# oresat0-1u-backplane.net
KiCad netlist of a schematic drawn in EAGLE
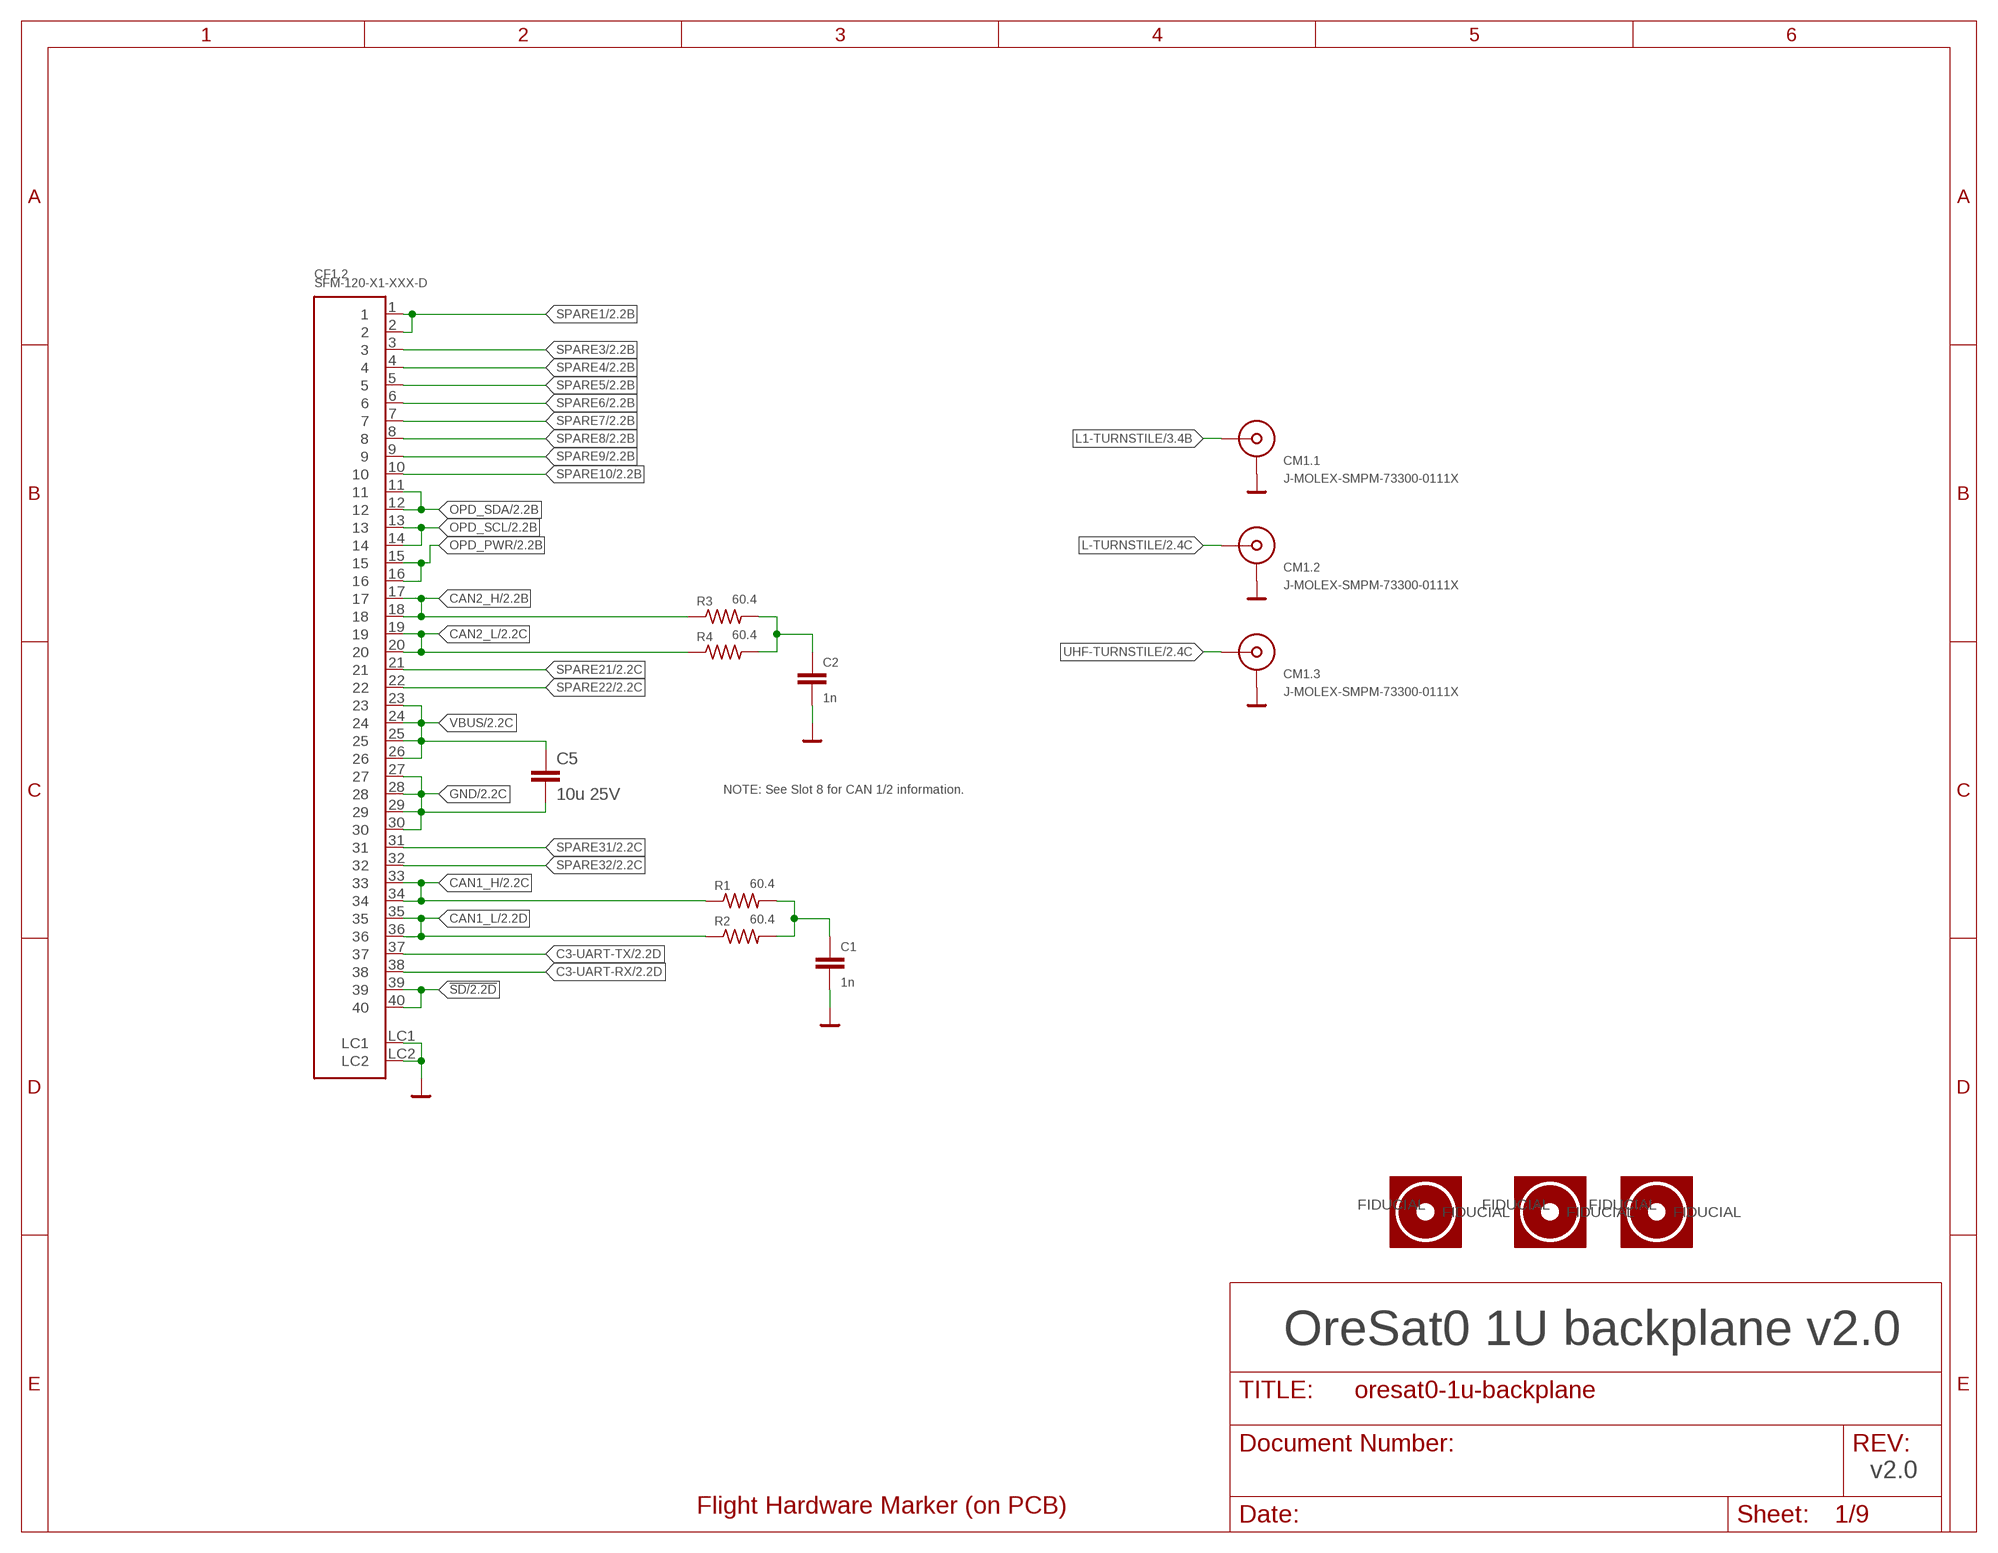
[diagram p0: schematic, sheet 1]
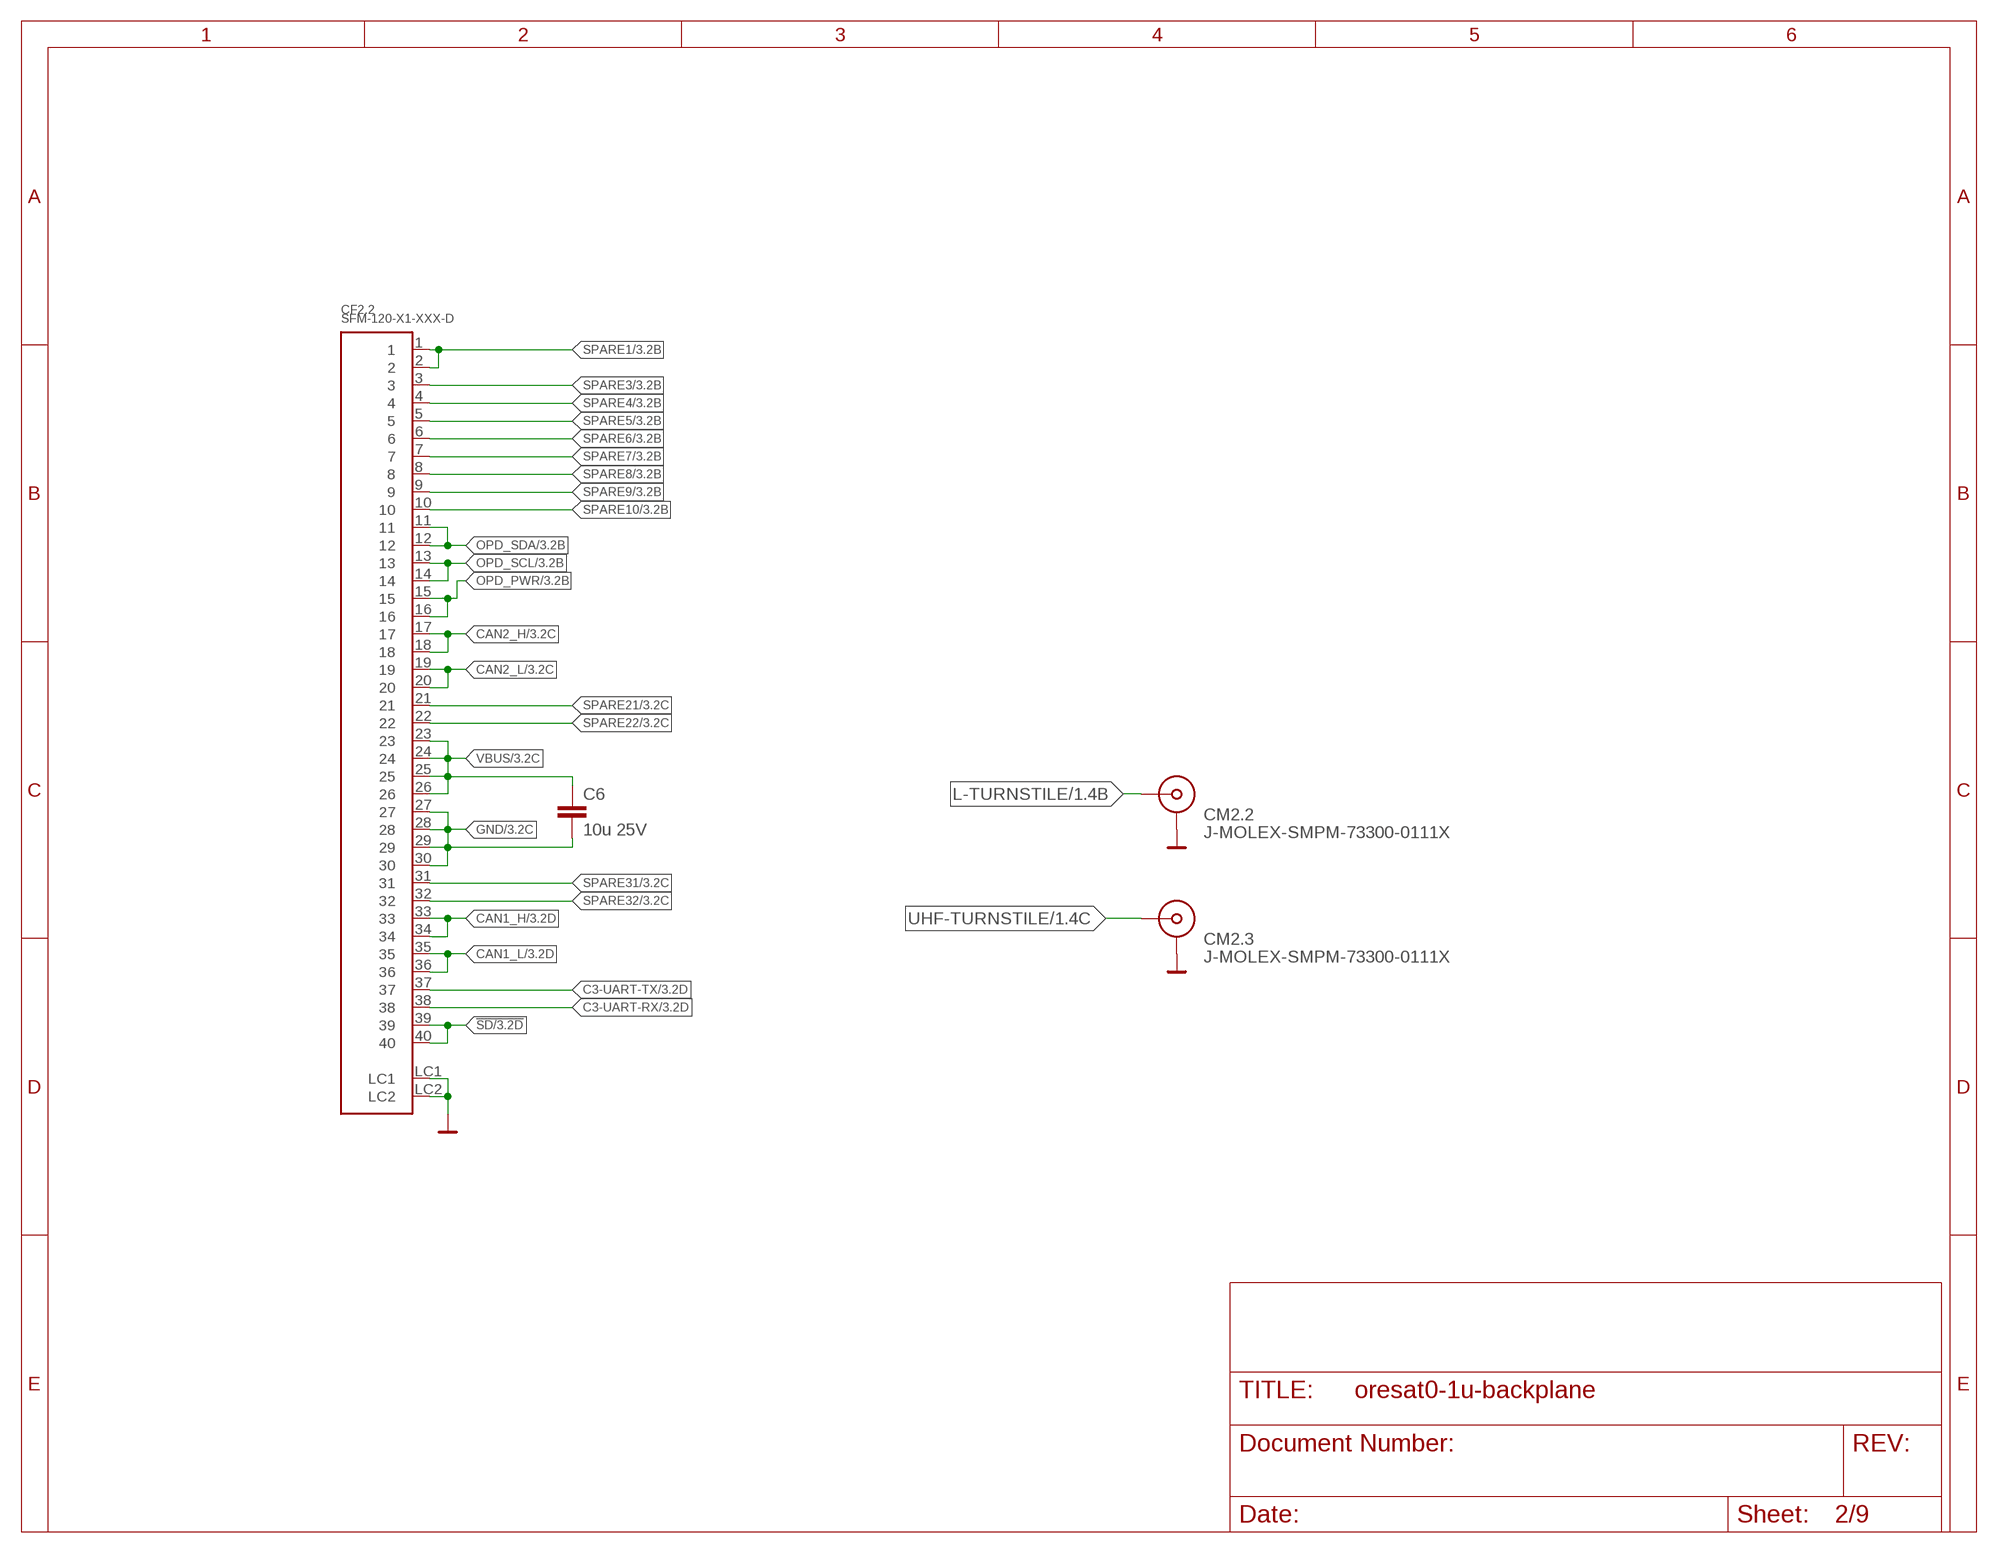
[diagram p1: schematic, sheet 2]
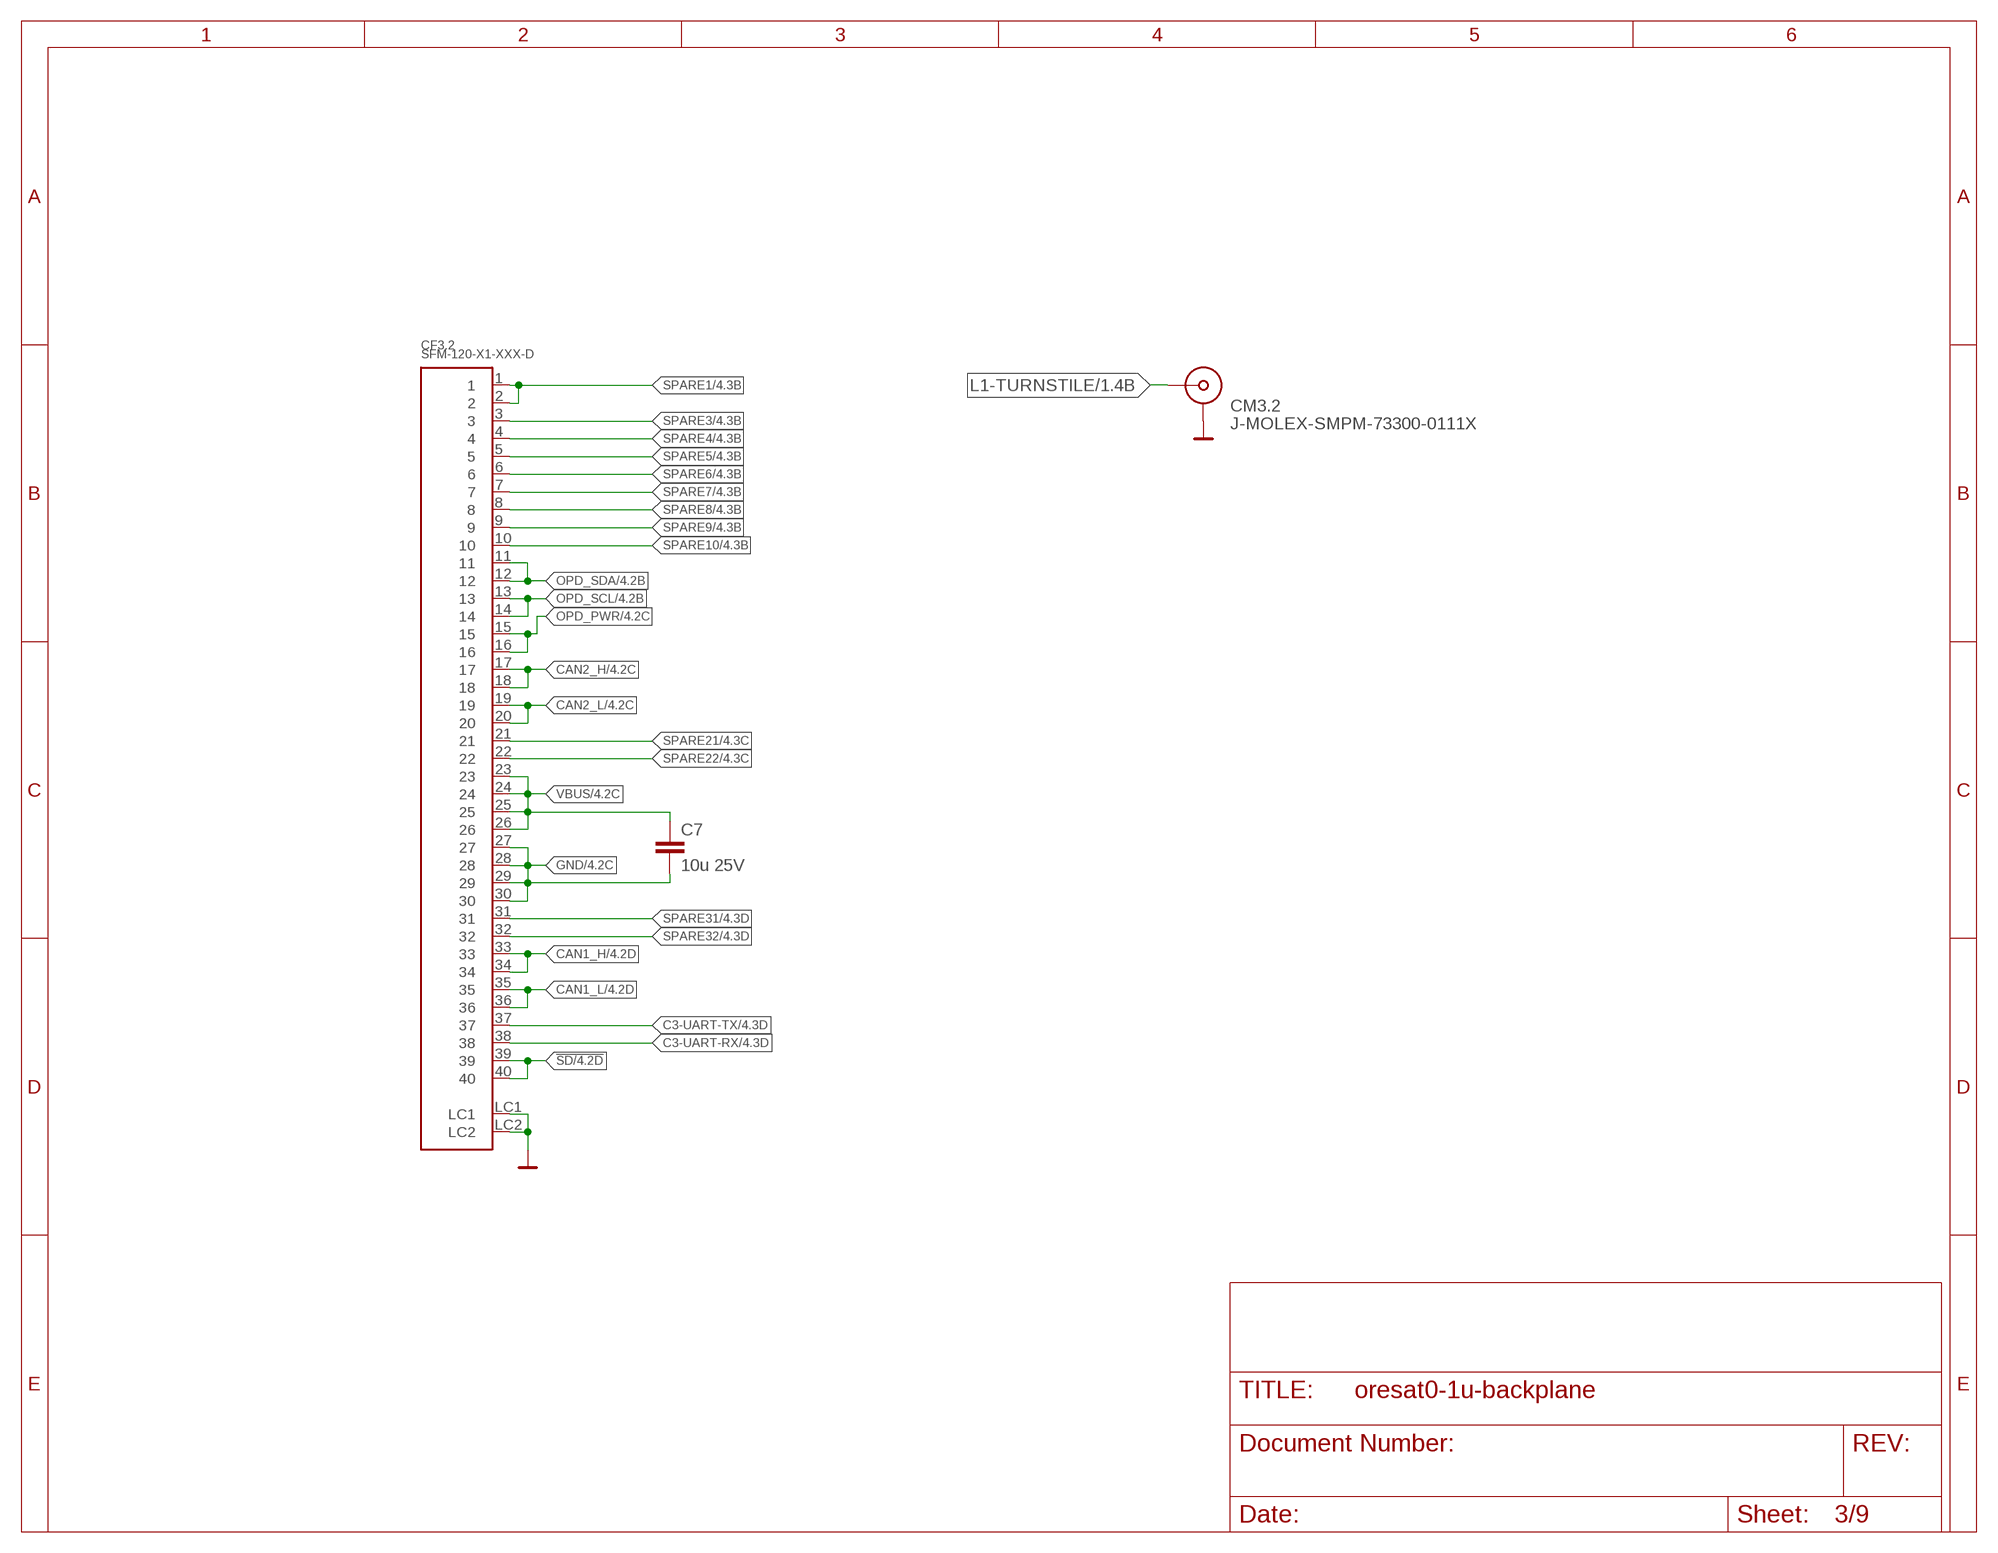
[diagram p2: schematic, sheet 3]
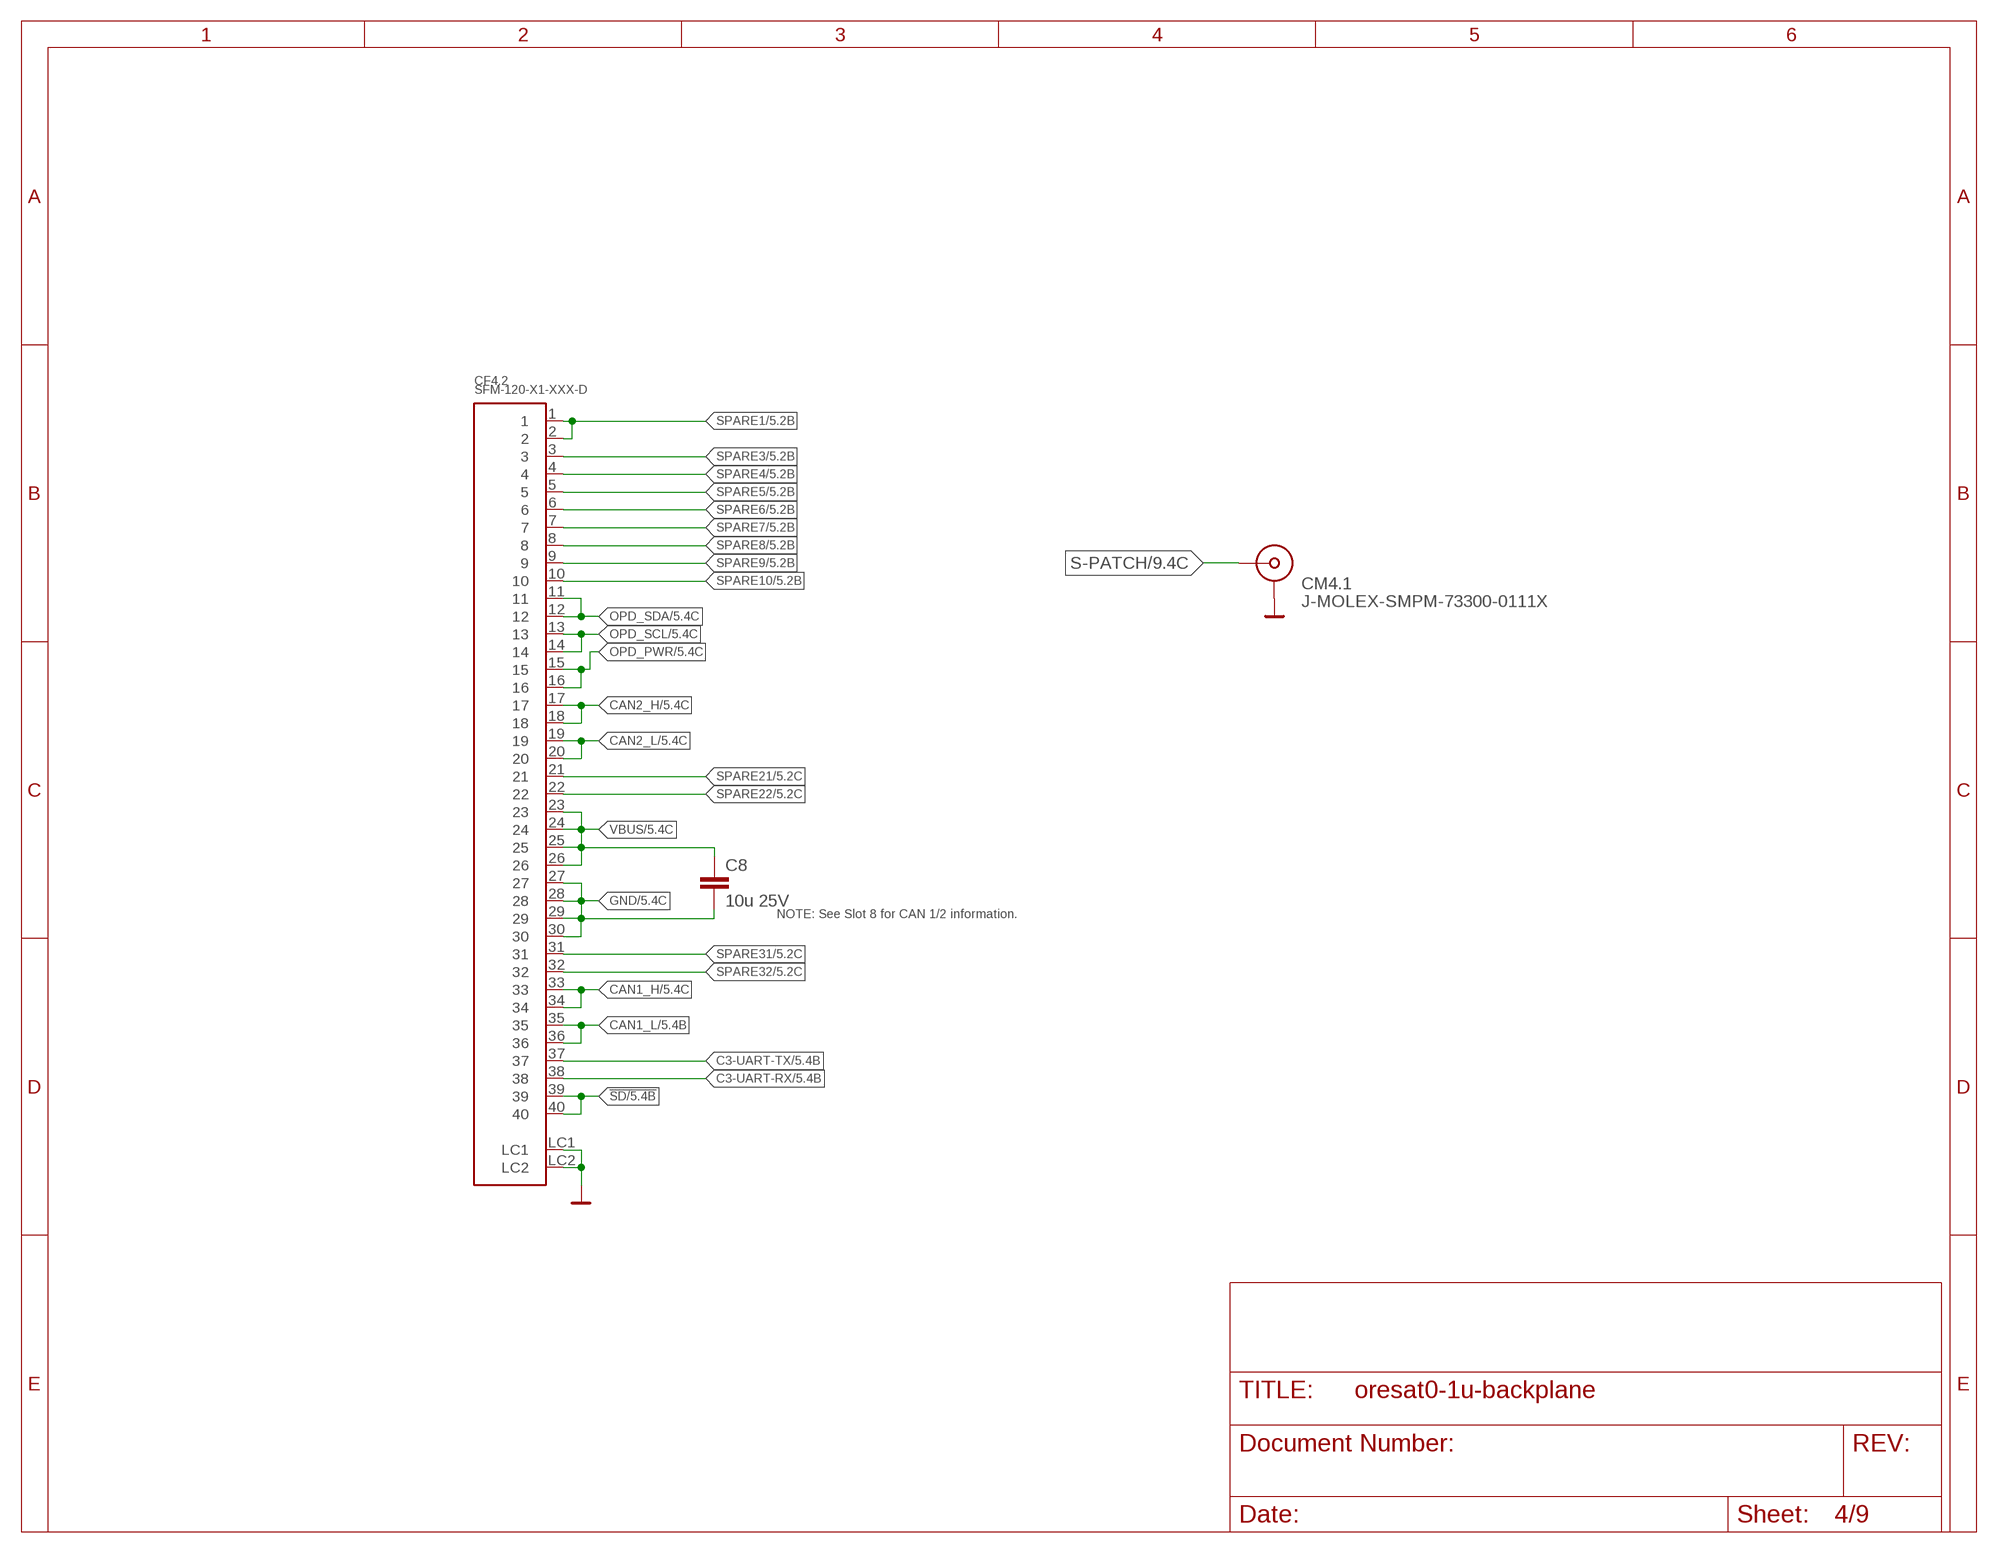
[diagram p3: schematic, sheet 4]
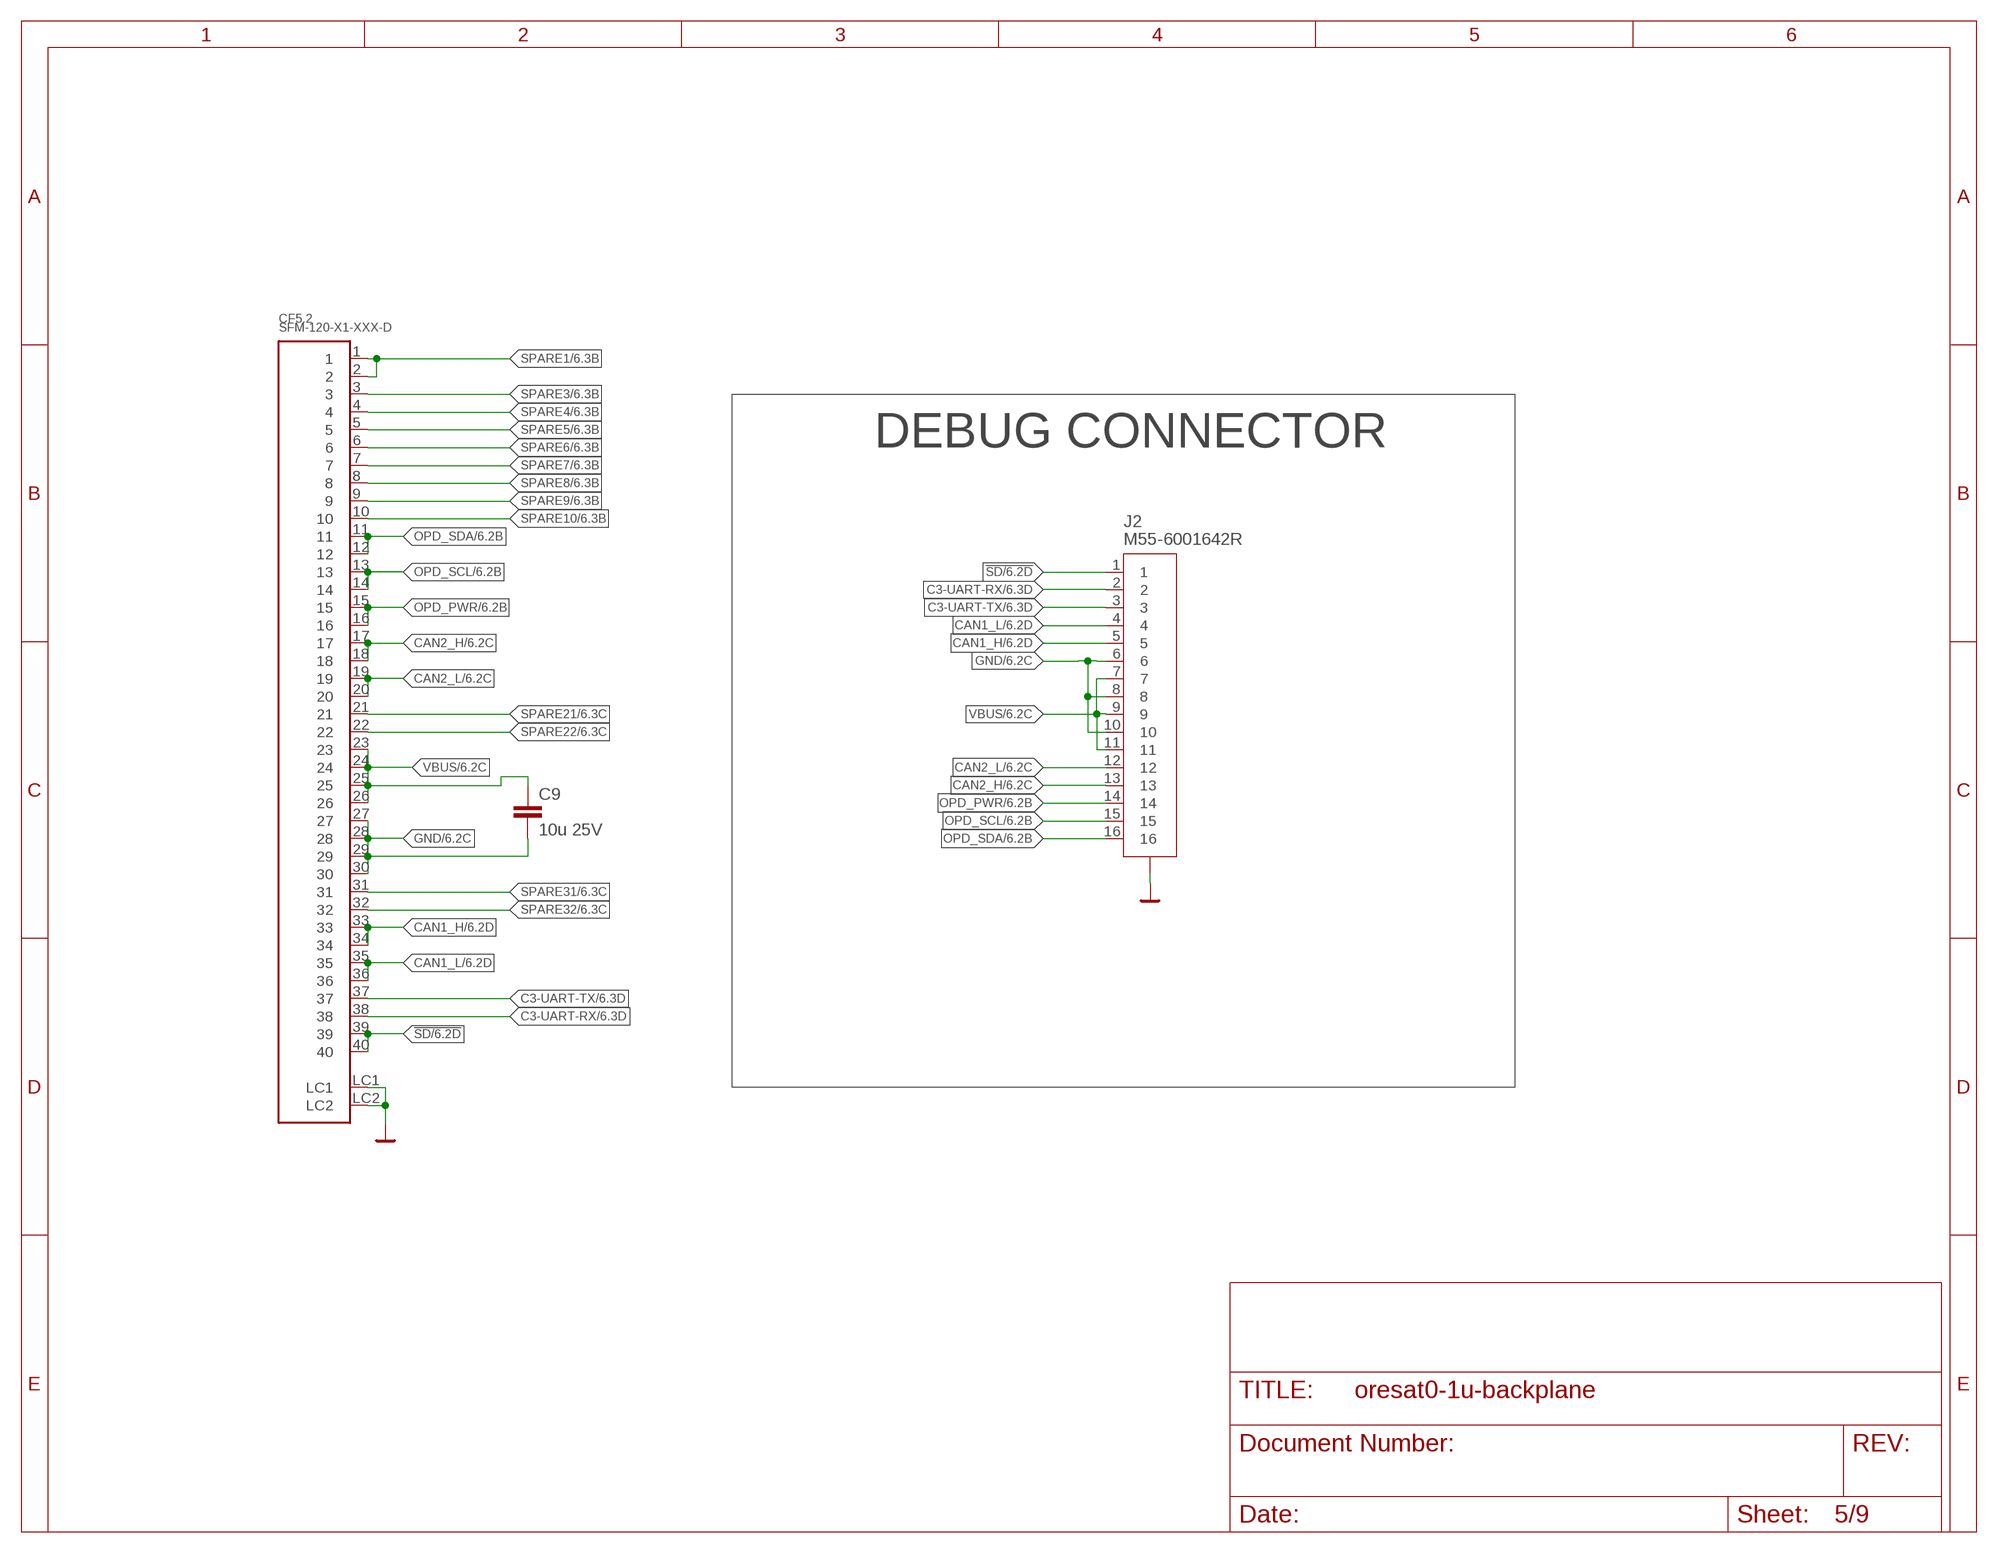
[diagram p4: schematic, sheet 5]
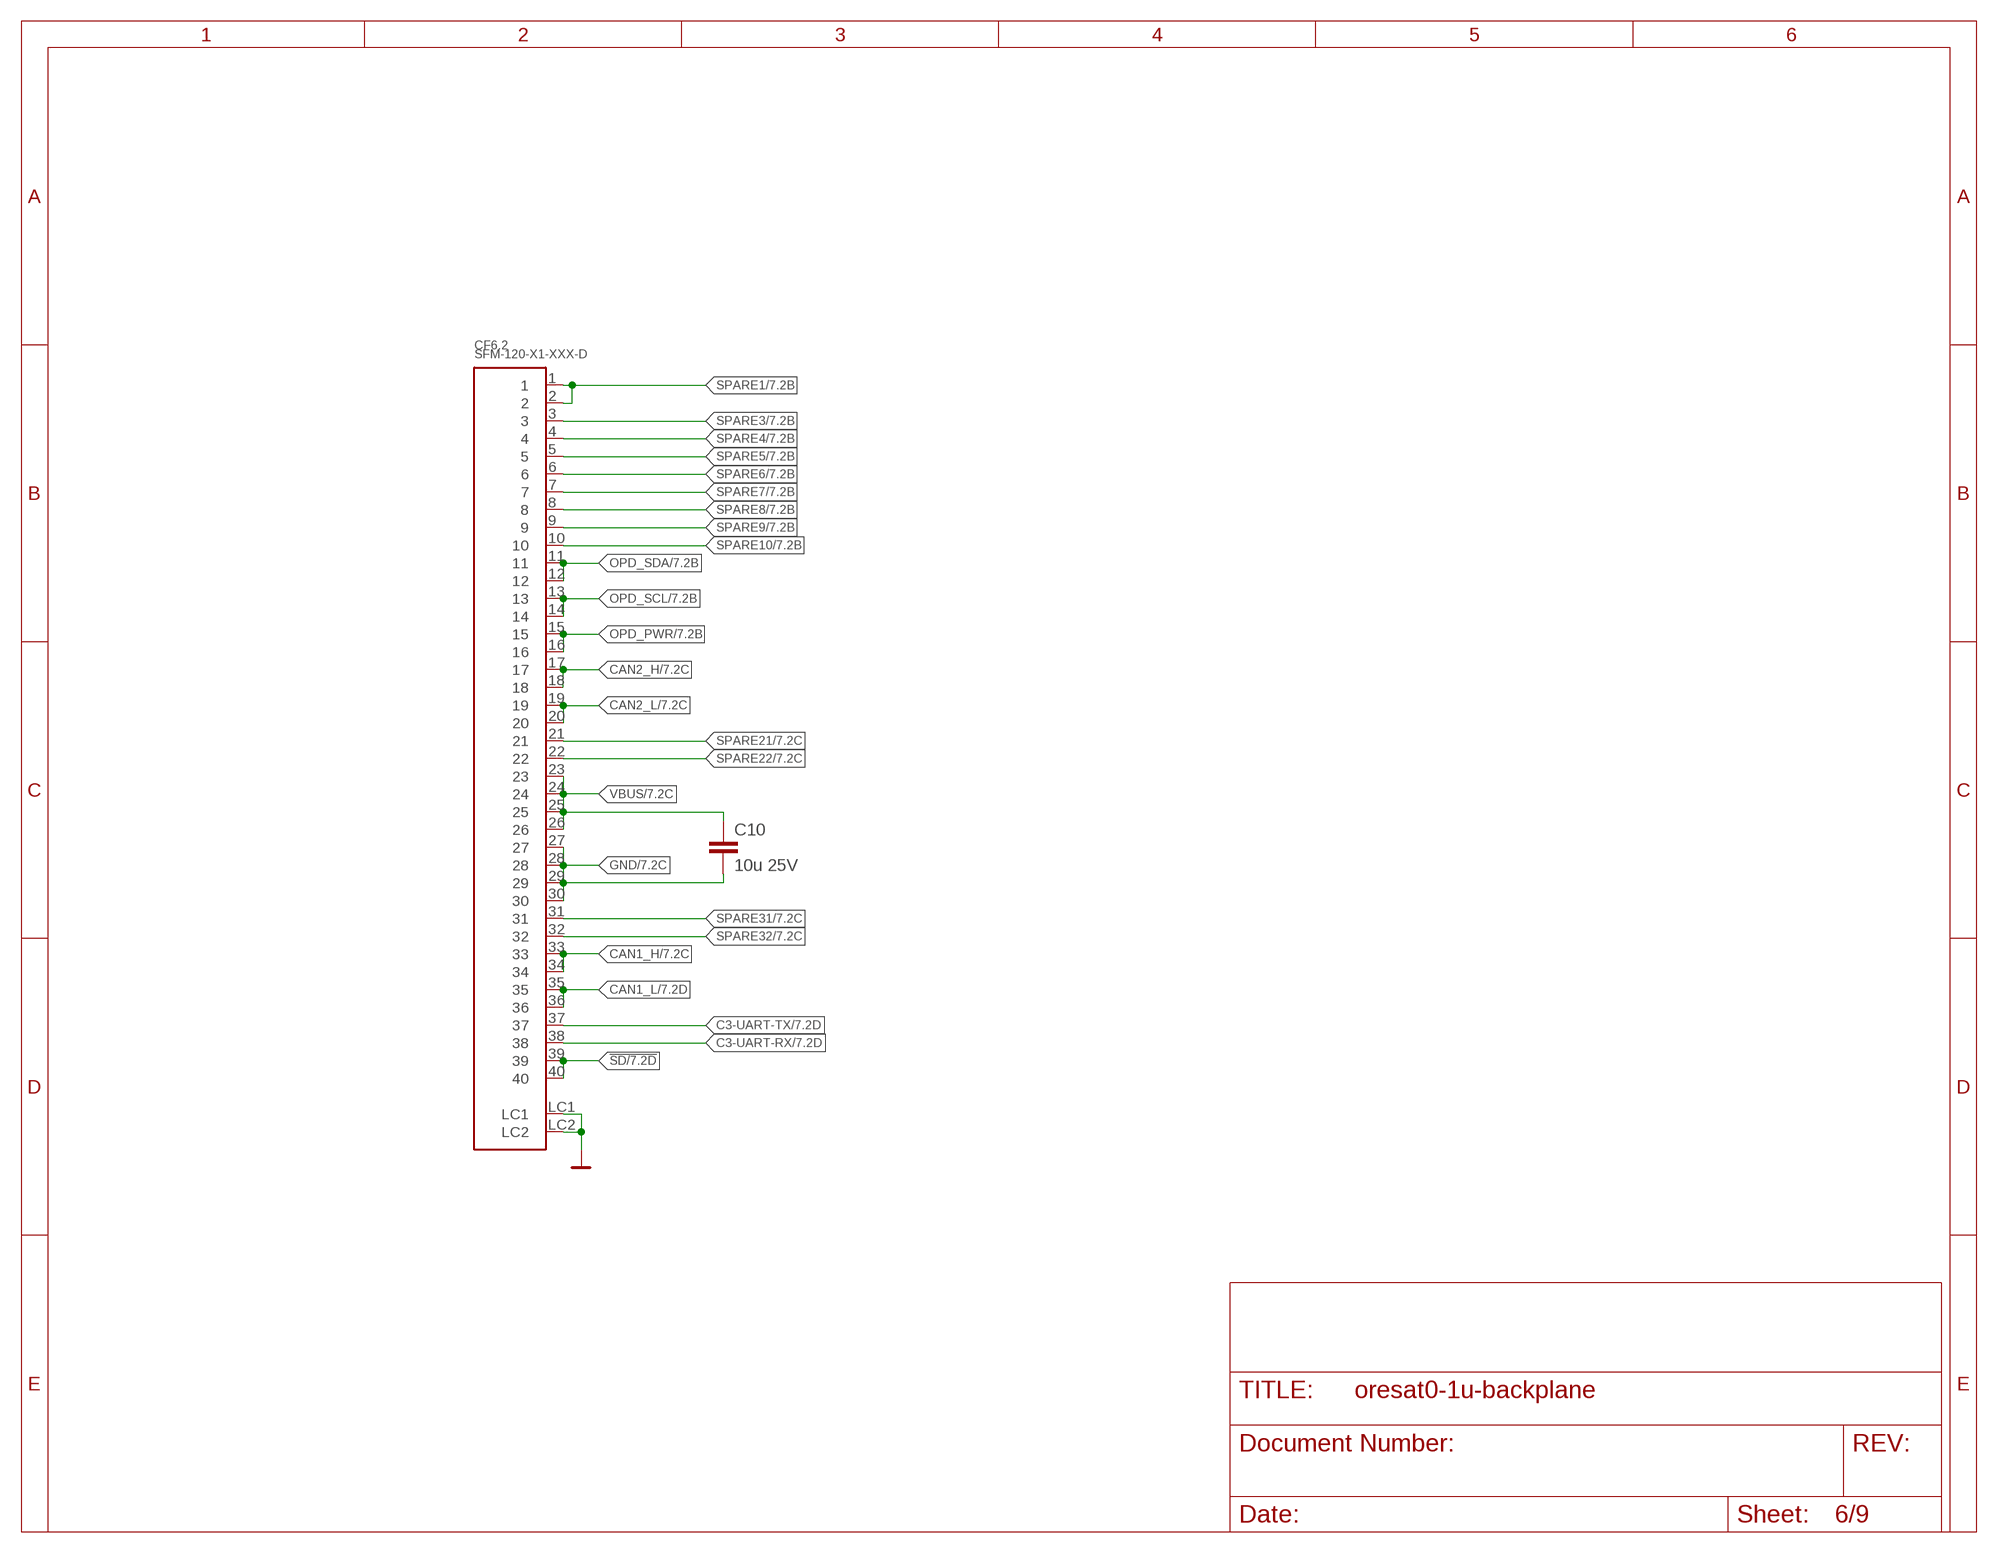
[diagram p5: schematic, sheet 6]
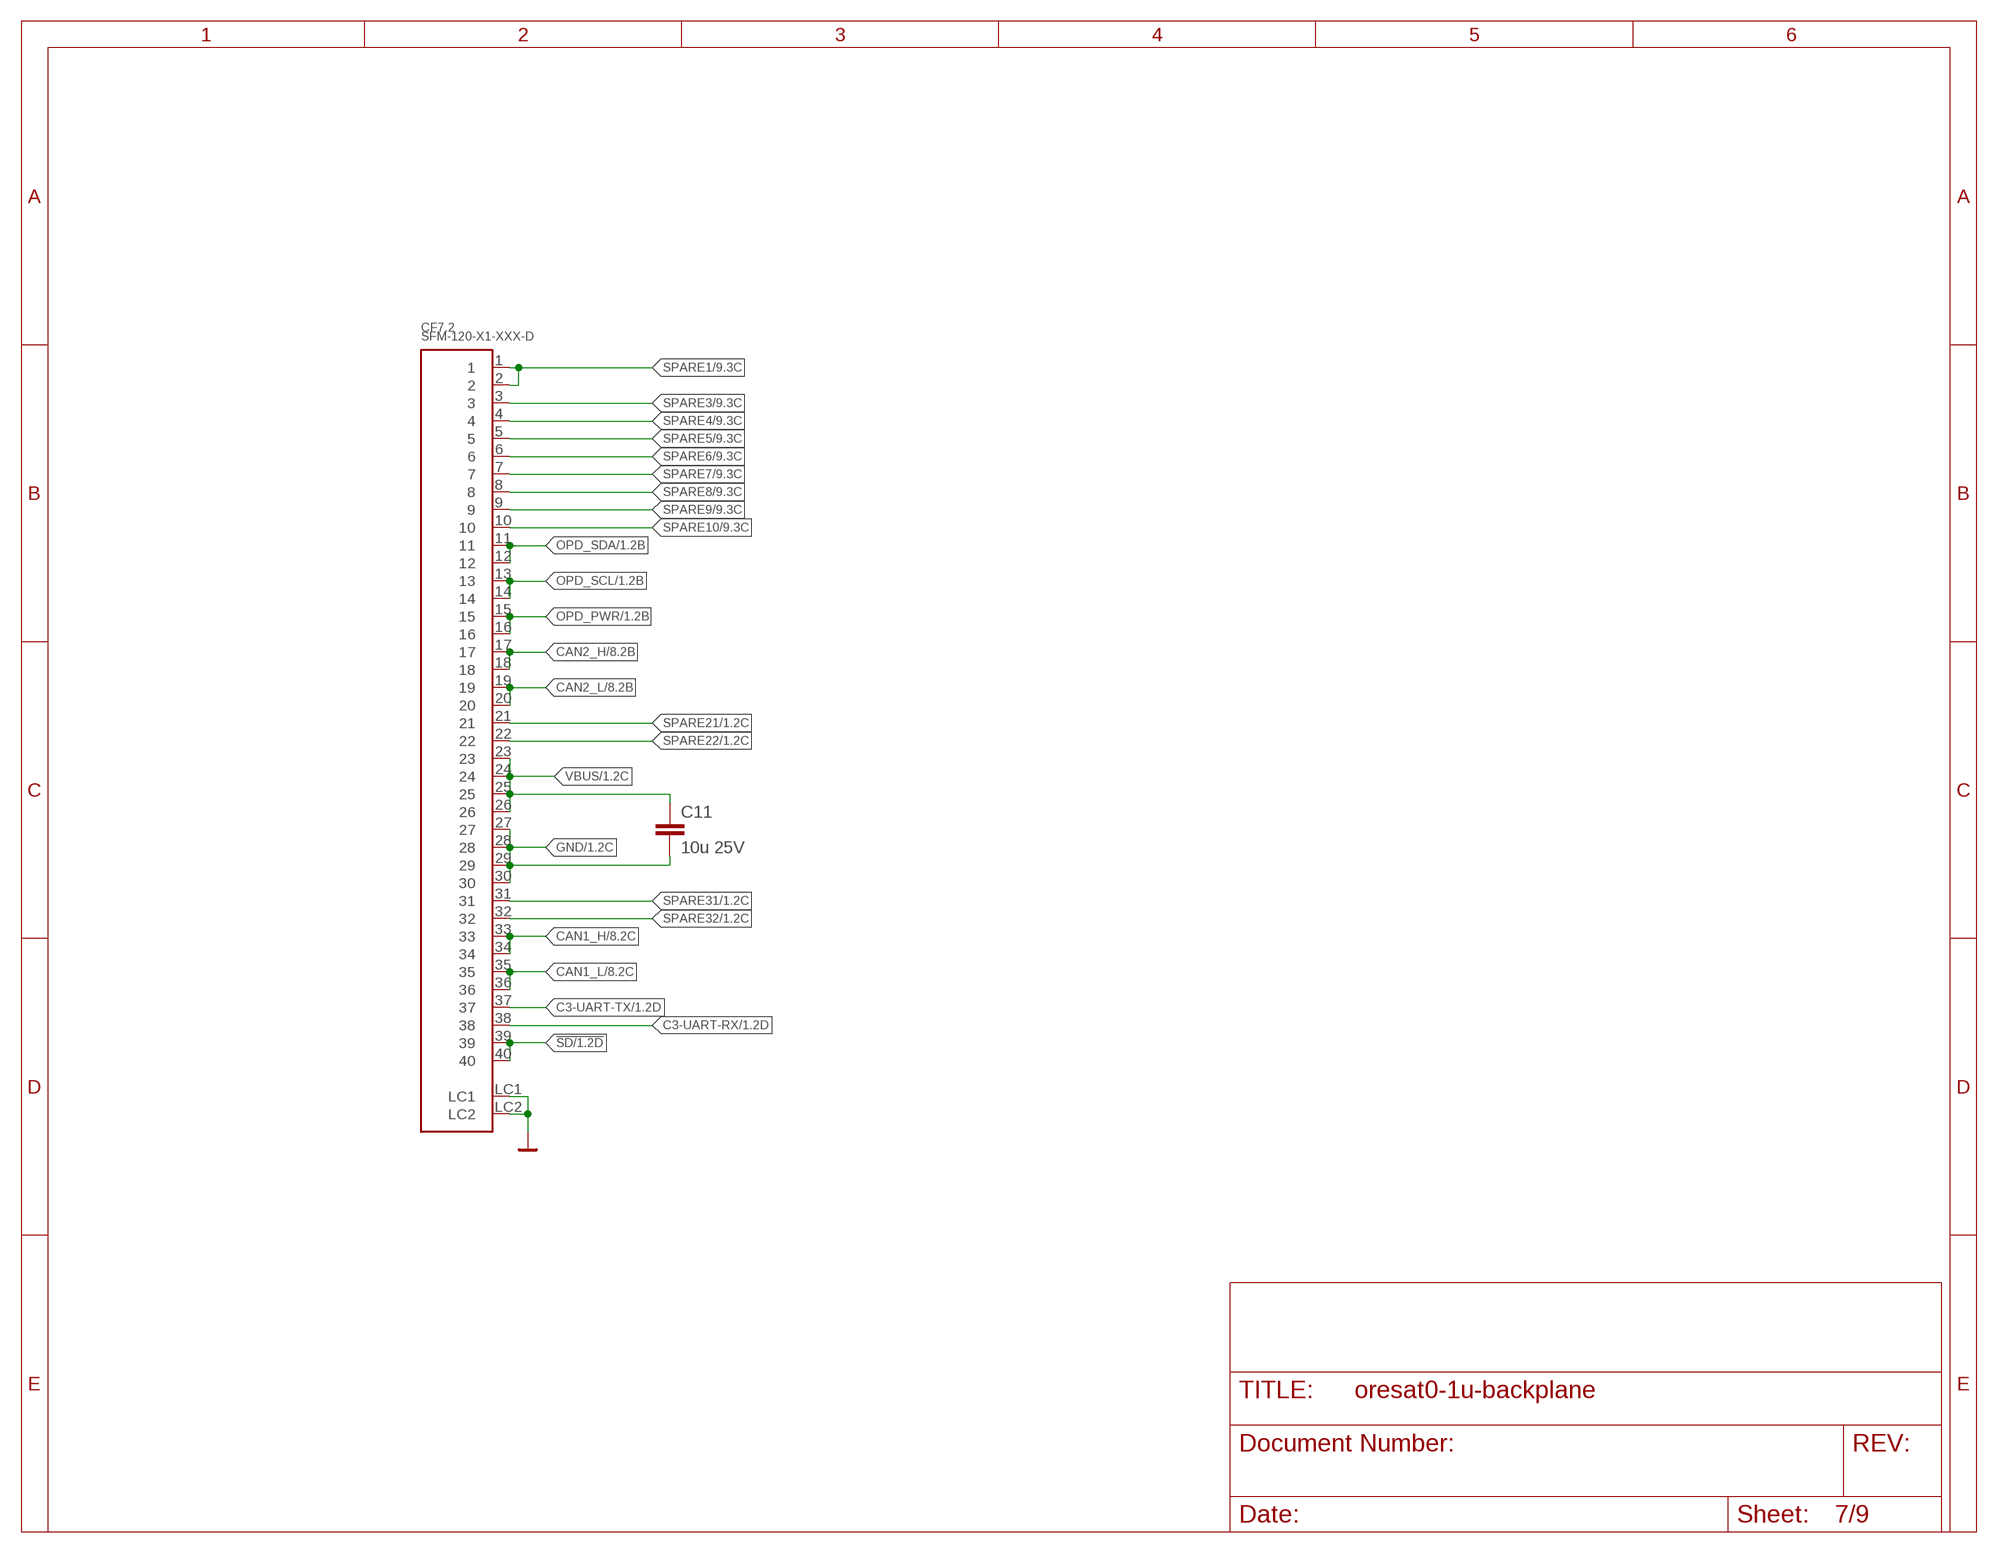
[diagram p6: schematic, sheet 7]
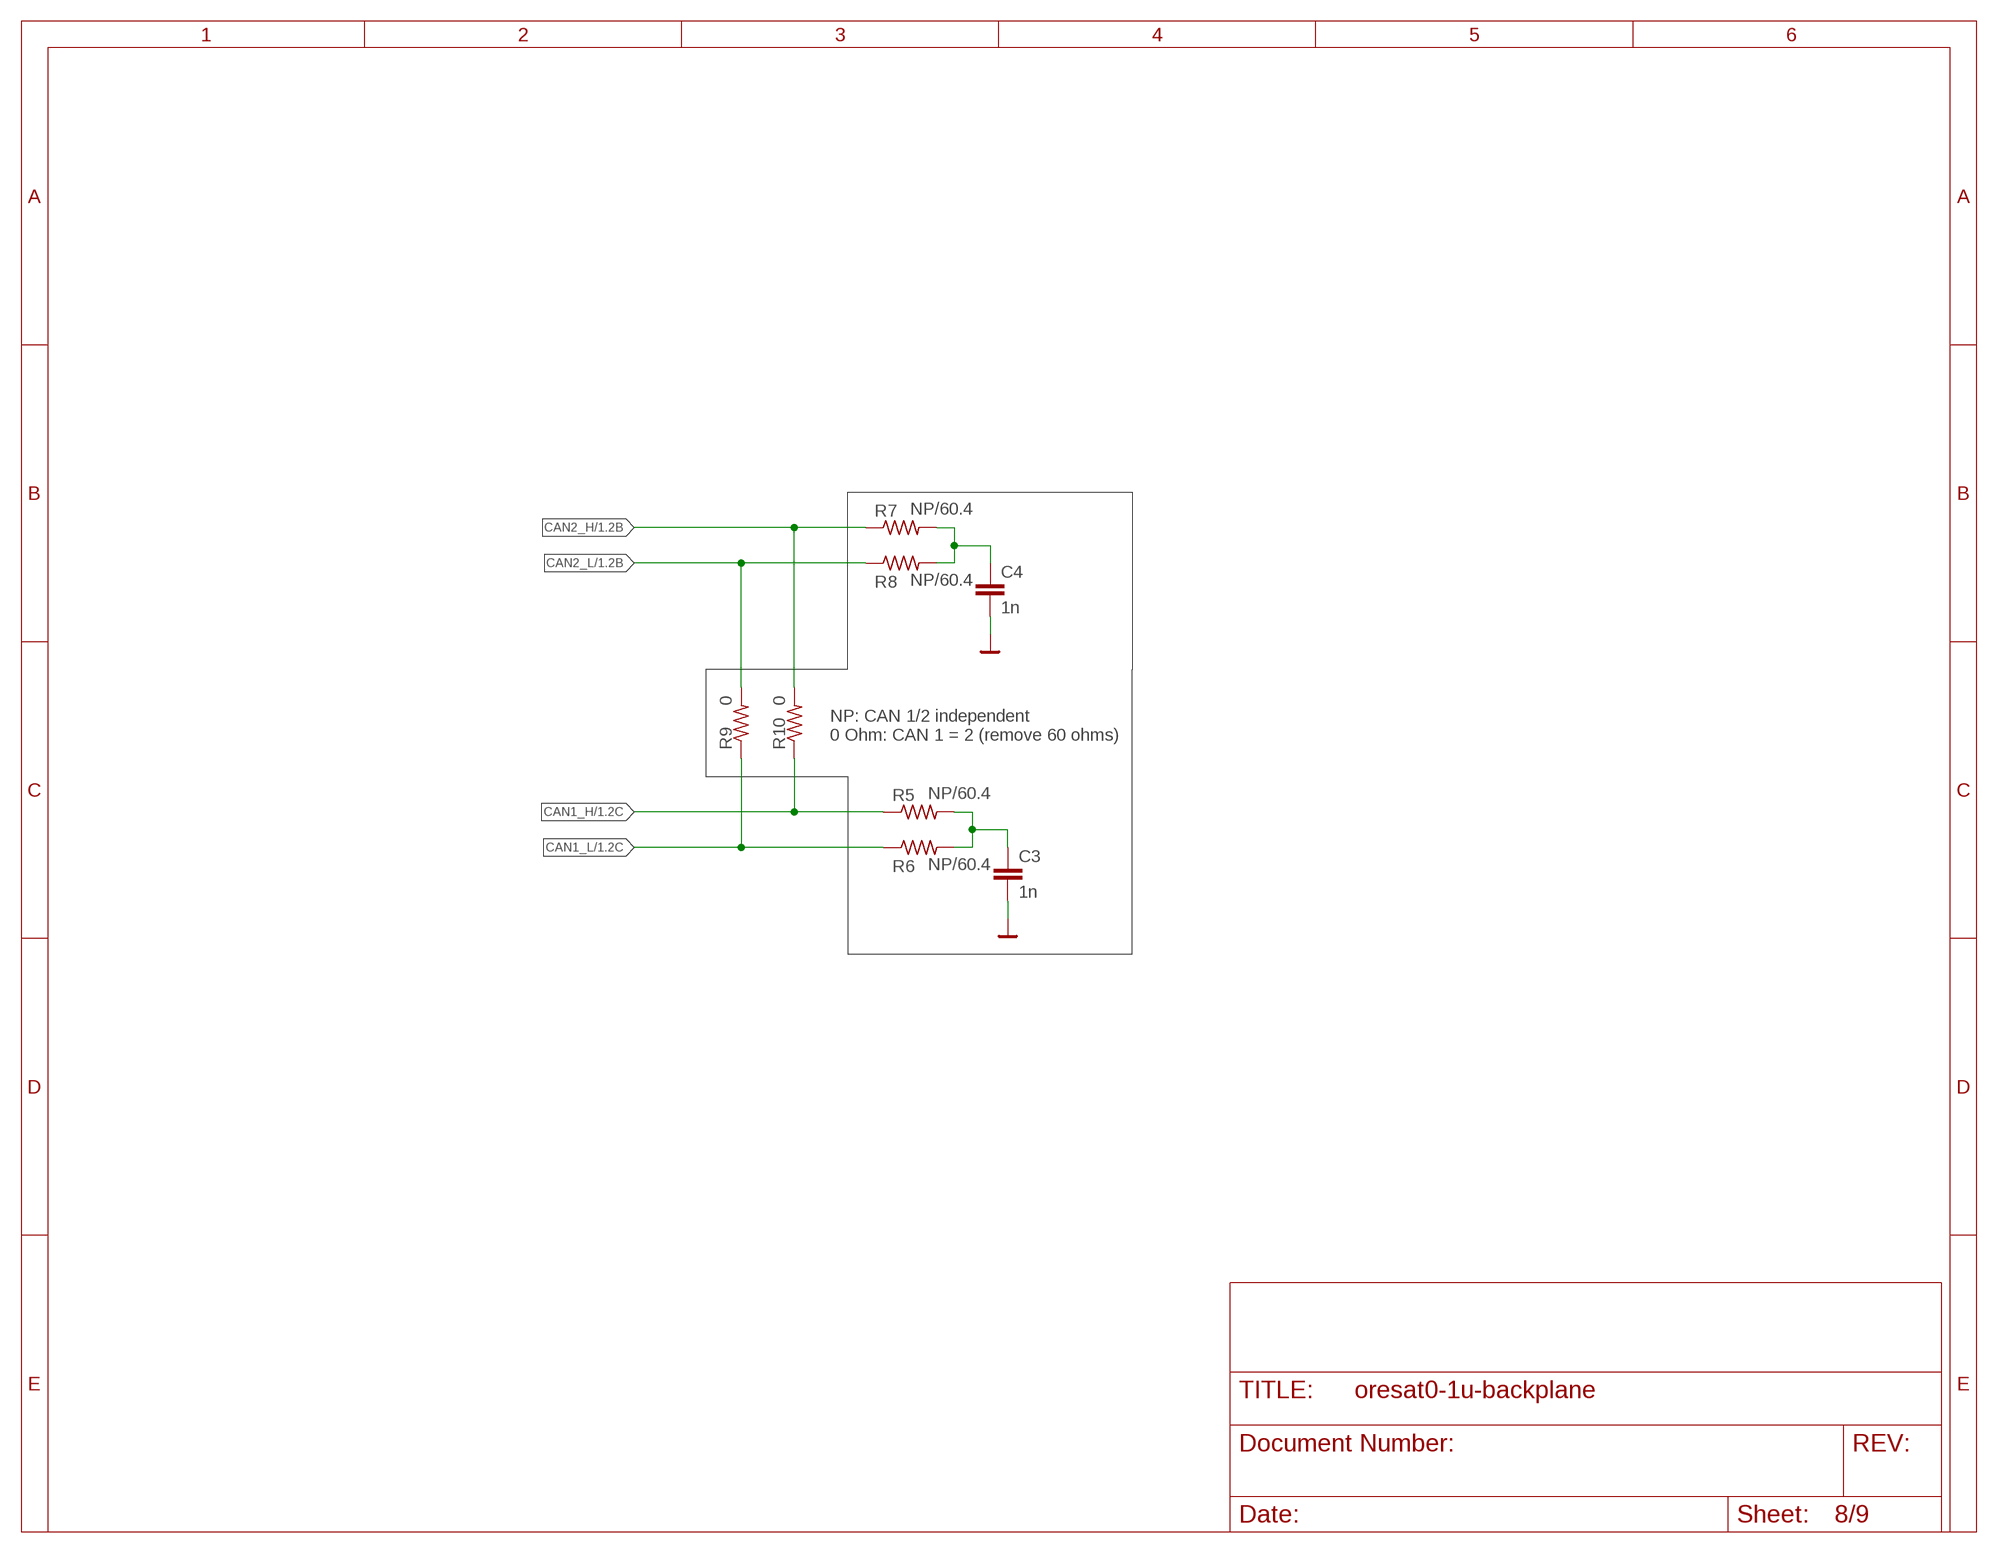
[diagram p7: schematic, sheet 8]
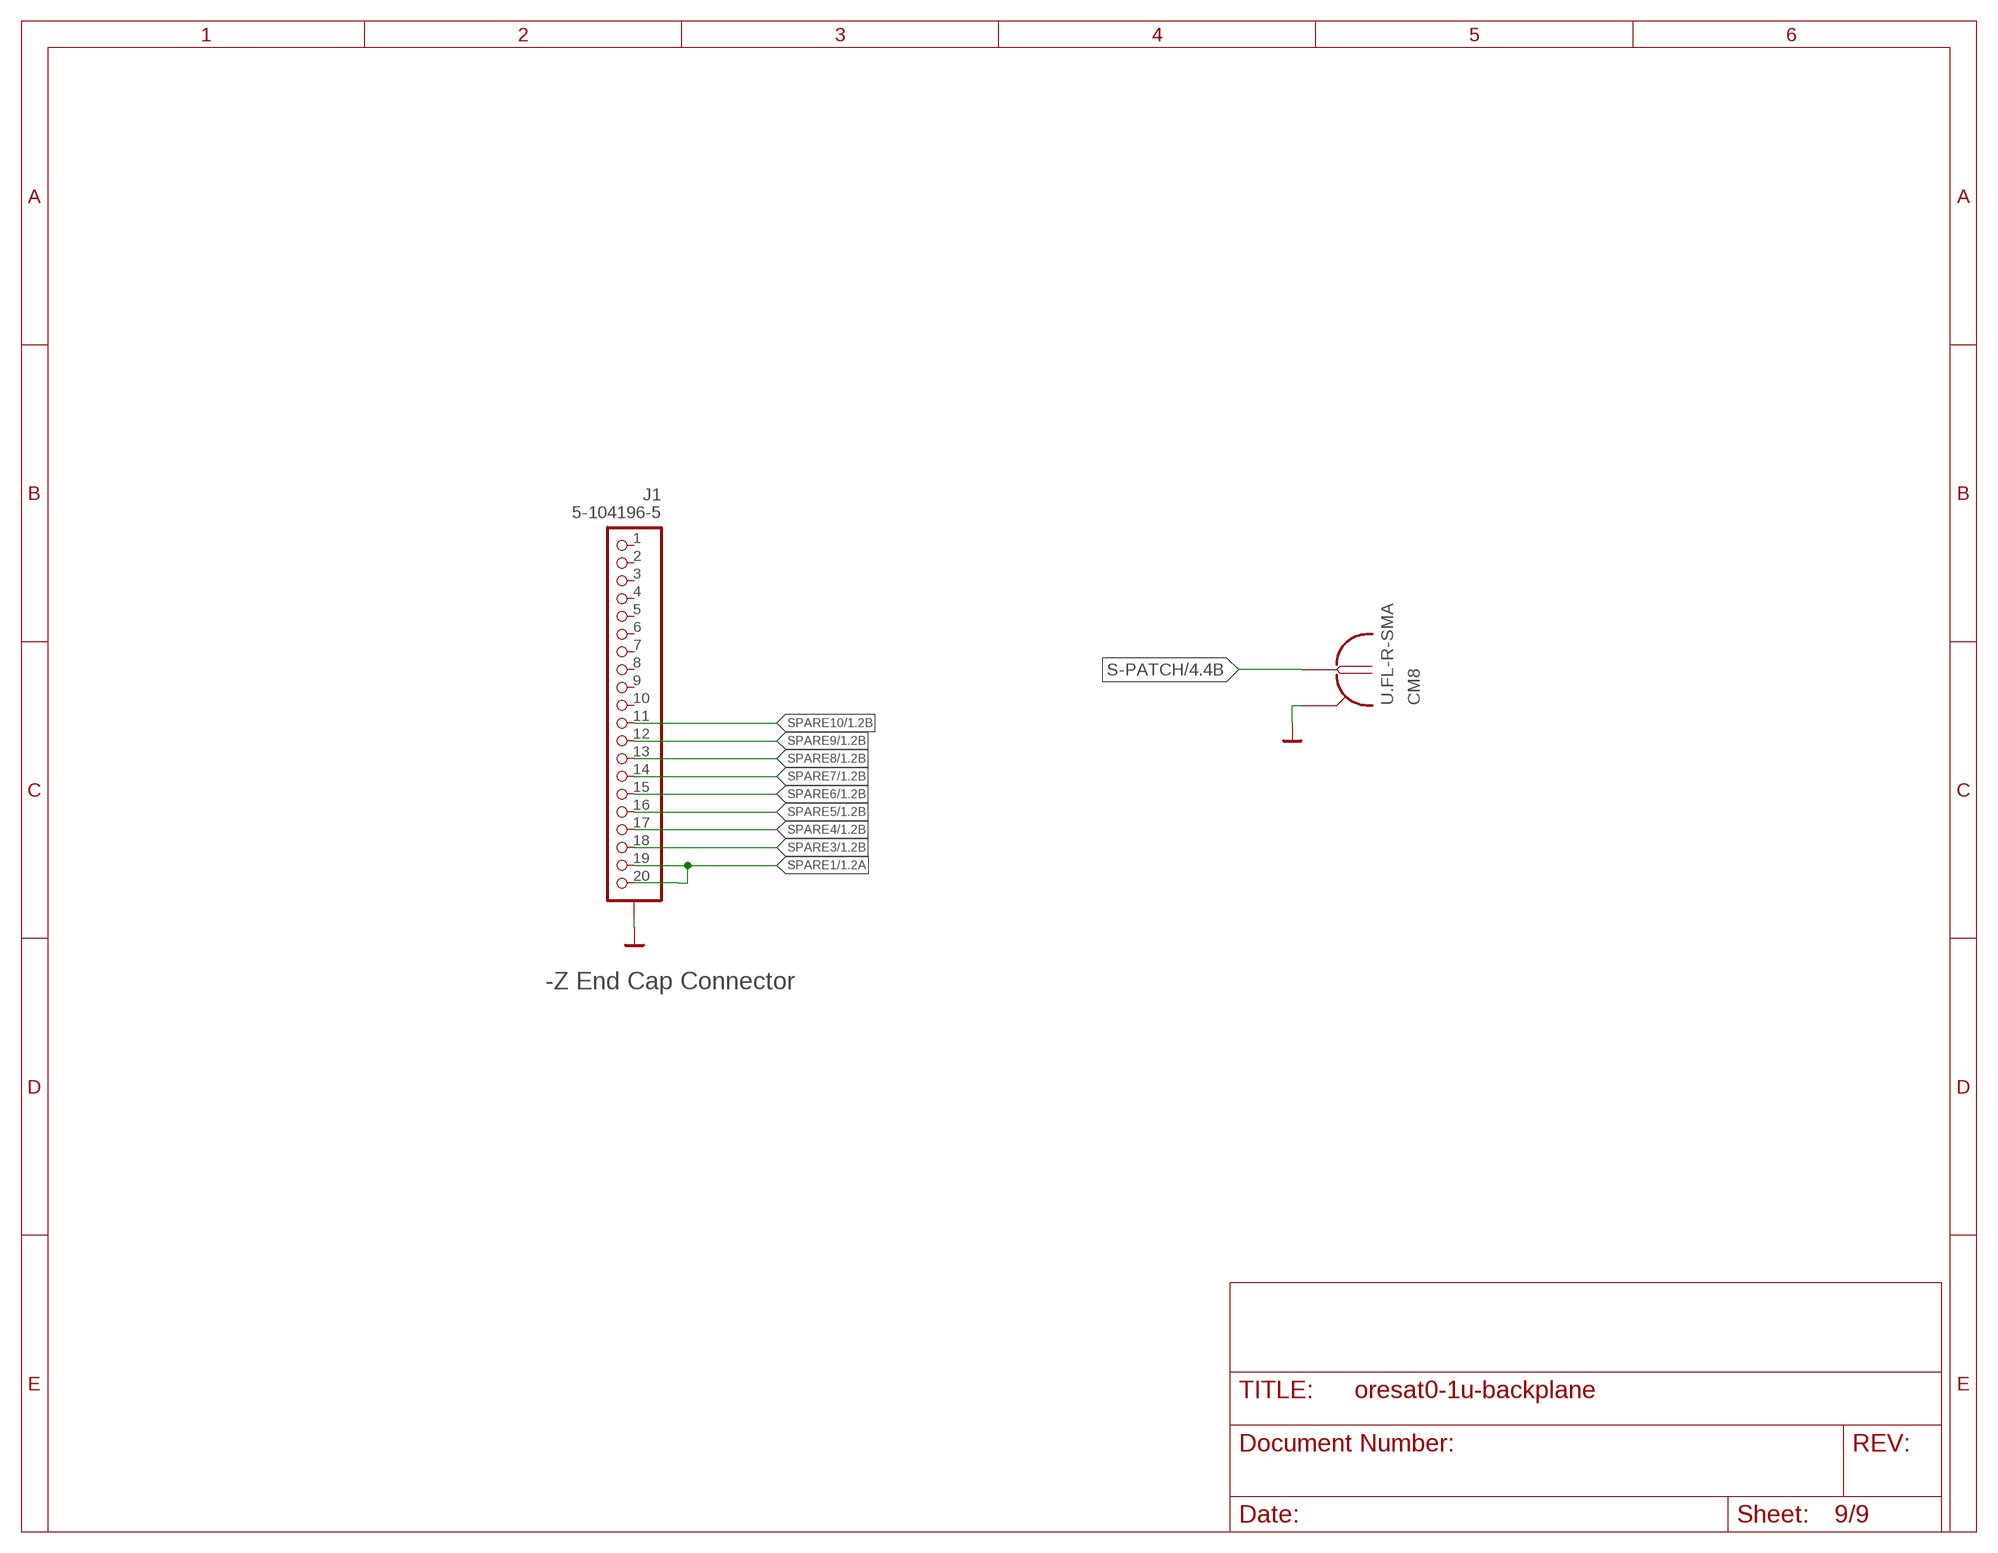
[diagram p8: schematic, sheet 9]

(export (version "E")
  (design (tool "Eeschema 10.0.6"))
  (components
    (comp (ref "C6")
      (value "10u 25V")
      (footprint "eagle-import:1206-B")
      (libsource (lib "eagle-import") (part "C-EU1206-B"))
    )
    (comp (ref "CF2.2")
      (value "SFM-120-X1-XXX-D")
      (footprint "eagle-import:SFM-120-X1-XXX-D")
      (libsource (lib "eagle-import") (part "SFM-120-X1-XXX-D"))
    )
    (comp (ref "CM2.2")
      (value "J-MOLEX-SMPM-73300-0111X")
      (footprint "eagle-import:J-MOLEX-SMPM-73300-0111X")
      (libsource (lib "eagle-import") (part "J-MOLEX-SMPM-73300-0111X"))
    )
    (comp (ref "CM2.3")
      (value "J-MOLEX-SMPM-73300-0111X")
      (footprint "eagle-import:J-MOLEX-SMPM-73300-0111X")
      (libsource (lib "eagle-import") (part "J-MOLEX-SMPM-73300-0111X"))
    )
    (comp (ref "C1")
      (value "1n")
      (footprint "eagle-import:.0603-C-NOSILK")
      (libsource (lib "eagle-import") (part "C-EU0603-C-NOSILK"))
    )
    (comp (ref "C2")
      (value "1n")
      (footprint "eagle-import:.0603-C-NOSILK")
      (libsource (lib "eagle-import") (part "C-EU0603-C-NOSILK"))
    )
    (comp (ref "C5")
      (value "10u 25V")
      (footprint "eagle-import:1206-B")
      (libsource (lib "eagle-import") (part "C-EU1206-B"))
    )
    (comp (ref "CF1.2")
      (value "SFM-120-X1-XXX-D")
      (footprint "eagle-import:SFM-120-X1-XXX-D")
      (libsource (lib "eagle-import") (part "SFM-120-X1-XXX-D"))
    )
    (comp (ref "CM1.1")
      (value "J-MOLEX-SMPM-73300-0111X")
      (footprint "eagle-import:J-MOLEX-SMPM-73300-0111X")
      (libsource (lib "eagle-import") (part "J-MOLEX-SMPM-73300-0111X"))
    )
    (comp (ref "CM1.2")
      (value "J-MOLEX-SMPM-73300-0111X")
      (footprint "eagle-import:J-MOLEX-SMPM-73300-0111X")
      (libsource (lib "eagle-import") (part "J-MOLEX-SMPM-73300-0111X"))
    )
    (comp (ref "CM1.3")
      (value "J-MOLEX-SMPM-73300-0111X")
      (footprint "eagle-import:J-MOLEX-SMPM-73300-0111X")
      (libsource (lib "eagle-import") (part "J-MOLEX-SMPM-73300-0111X"))
    )
    (comp (ref "FIDUCIAL1")
      (value "FIDUCIAL-1.0X2.0")
      (footprint "eagle-import:FIDUCIAL-1.0X2.0")
      (libsource (lib "eagle-import") (part "FIDUCIAL-1.0X2.0"))
    )
    (comp (ref "FIDUCIAL2")
      (value "FIDUCIAL-1.0X2.0")
      (footprint "eagle-import:FIDUCIAL-1.0X2.0")
      (libsource (lib "eagle-import") (part "FIDUCIAL-1.0X2.0"))
    )
    (comp (ref "FIDUCIAL3")
      (value "FIDUCIAL-1.0X2.0")
      (footprint "eagle-import:FIDUCIAL-1.0X2.0")
      (libsource (lib "eagle-import") (part "FIDUCIAL-1.0X2.0"))
    )
    (comp (ref "R1")
      (value "60.4")
      (footprint "eagle-import:1206-C")
      (libsource (lib "eagle-import") (part "R-US_1206-C"))
    )
    (comp (ref "R2")
      (value "60.4")
      (footprint "eagle-import:1206-C")
      (libsource (lib "eagle-import") (part "R-US_1206-C"))
    )
    (comp (ref "R3")
      (value "60.4")
      (footprint "eagle-import:1206-C")
      (libsource (lib "eagle-import") (part "R-US_1206-C"))
    )
    (comp (ref "R4")
      (value "60.4")
      (footprint "eagle-import:1206-C")
      (libsource (lib "eagle-import") (part "R-US_1206-C"))
    )
    (comp (ref "U$1")
      (value "FLIGHMARKERNEW")
      (footprint "eagle-import:FLIGHTMARKER_NEW_BOARDS")
      (libsource (lib "eagle-import") (part "FLIGHMARKERNEW"))
    )
    (comp (ref "C8")
      (value "10u 25V")
      (footprint "eagle-import:1206-B")
      (libsource (lib "eagle-import") (part "C-EU1206-B"))
    )
    (comp (ref "CF4.2")
      (value "SFM-120-X1-XXX-D")
      (footprint "eagle-import:SFM-120-X1-XXX-D")
      (libsource (lib "eagle-import") (part "SFM-120-X1-XXX-D"))
    )
    (comp (ref "CM4.1")
      (value "J-MOLEX-SMPM-73300-0111X")
      (footprint "eagle-import:J-MOLEX-SMPM-73300-0111X")
      (libsource (lib "eagle-import") (part "J-MOLEX-SMPM-73300-0111X"))
    )
    (comp (ref "C3")
      (value "1n")
      (footprint "eagle-import:.0603-C-NOSILK")
      (libsource (lib "eagle-import") (part "C-EU0603-C-NOSILK"))
    )
    (comp (ref "C4")
      (value "1n")
      (footprint "eagle-import:.0603-C-NOSILK")
      (libsource (lib "eagle-import") (part "C-EU0603-C-NOSILK"))
    )
    (comp (ref "R5")
      (value "NP/60.4")
      (footprint "eagle-import:1206-C")
      (libsource (lib "eagle-import") (part "R-US_1206-C"))
    )
    (comp (ref "R6")
      (value "NP/60.4")
      (footprint "eagle-import:1206-C")
      (libsource (lib "eagle-import") (part "R-US_1206-C"))
    )
    (comp (ref "R7")
      (value "NP/60.4")
      (footprint "eagle-import:1206-C")
      (libsource (lib "eagle-import") (part "R-US_1206-C"))
    )
    (comp (ref "R8")
      (value "NP/60.4")
      (footprint "eagle-import:1206-C")
      (libsource (lib "eagle-import") (part "R-US_1206-C"))
    )
    (comp (ref "R9")
      (value "0")
      (footprint "eagle-import:.0603-B-NOSILK")
      (libsource (lib "eagle-import") (part "R-US_0603-B-NOSILK"))
    )
    (comp (ref "R10")
      (value "0")
      (footprint "eagle-import:.0603-B-NOSILK")
      (libsource (lib "eagle-import") (part "R-US_0603-B-NOSILK"))
    )
    (comp (ref "C9")
      (value "10u 25V")
      (footprint "eagle-import:1206-B")
      (libsource (lib "eagle-import") (part "C-EU1206-B"))
    )
    (comp (ref "CF5.2")
      (value "SFM-120-X1-XXX-D")
      (footprint "eagle-import:SFM-120-X1-XXX-D")
      (libsource (lib "eagle-import") (part "SFM-120-X1-XXX-D"))
    )
    (comp (ref "J2")
      (value "M55-6001642R")
      (footprint "eagle-import:CONN_M55-6001642R_HRW")
      (fields (field (name "COPYRIGHT") "Copyright (C) 2021 Ultra Librarian. All rights reserved."))
      (libsource (lib "eagle-import") (part "M55-6001642R"))
    )
    (comp (ref "C11")
      (value "10u 25V")
      (footprint "eagle-import:1206-B")
      (libsource (lib "eagle-import") (part "C-EU1206-B"))
    )
    (comp (ref "CF7.2")
      (value "SFM-120-X1-XXX-D")
      (footprint "eagle-import:SFM-120-X1-XXX-D")
      (libsource (lib "eagle-import") (part "SFM-120-X1-XXX-D"))
    )
    (comp (ref "C7")
      (value "10u 25V")
      (footprint "eagle-import:1206-B")
      (libsource (lib "eagle-import") (part "C-EU1206-B"))
    )
    (comp (ref "CF3.2")
      (value "SFM-120-X1-XXX-D")
      (footprint "eagle-import:SFM-120-X1-XXX-D")
      (libsource (lib "eagle-import") (part "SFM-120-X1-XXX-D"))
    )
    (comp (ref "CM3.2")
      (value "J-MOLEX-SMPM-73300-0111X")
      (footprint "eagle-import:J-MOLEX-SMPM-73300-0111X")
      (libsource (lib "eagle-import") (part "J-MOLEX-SMPM-73300-0111X"))
    )
    (comp (ref "C10")
      (value "10u 25V")
      (footprint "eagle-import:1206-B")
      (libsource (lib "eagle-import") (part "C-EU1206-B"))
    )
    (comp (ref "CF6.2")
      (value "SFM-120-X1-XXX-D")
      (footprint "eagle-import:SFM-120-X1-XXX-D")
      (libsource (lib "eagle-import") (part "SFM-120-X1-XXX-D"))
    )
    (comp (ref "CM8")
      (value "U.FL-R-SMA")
      (footprint "eagle-import:U.FL-R-SMT")
      (libsource (lib "eagle-import") (part "U.FL-R-SMA"))
    )
    (comp (ref "J1")
      (value "5-104196-5")
      (footprint "eagle-import:5-104196-5")
      (libsource (lib "eagle-import") (part "5-104196-5"))
    )
  )
  (nets
    (net (code "1") (name "C3-UART-RX") (class "Default")
      (node (ref "CF1.2") (pin "38") (pinfunction "38_38") (pintype "passive"))
      (node (ref "CF2.2") (pin "38") (pinfunction "38_38") (pintype "passive"))
      (node (ref "CF3.2") (pin "38") (pinfunction "38_38") (pintype "passive"))
      (node (ref "CF4.2") (pin "38") (pinfunction "38_38") (pintype "passive"))
      (node (ref "CF5.2") (pin "38") (pinfunction "38_38") (pintype "passive"))
      (node (ref "CF6.2") (pin "38") (pinfunction "38_38") (pintype "passive"))
      (node (ref "CF7.2") (pin "38") (pinfunction "38_38") (pintype "passive"))
      (node (ref "J2") (pin "2") (pinfunction "2_2") (pintype "passive"))
    )
    (net (code "2") (name "C3-UART-TX") (class "Default")
      (node (ref "CF1.2") (pin "37") (pinfunction "37_37") (pintype "passive"))
      (node (ref "CF2.2") (pin "37") (pinfunction "37_37") (pintype "passive"))
      (node (ref "CF3.2") (pin "37") (pinfunction "37_37") (pintype "passive"))
      (node (ref "CF4.2") (pin "37") (pinfunction "37_37") (pintype "passive"))
      (node (ref "CF5.2") (pin "37") (pinfunction "37_37") (pintype "passive"))
      (node (ref "CF6.2") (pin "37") (pinfunction "37_37") (pintype "passive"))
      (node (ref "CF7.2") (pin "37") (pinfunction "37_37") (pintype "passive"))
      (node (ref "J2") (pin "3") (pinfunction "3_3") (pintype "passive"))
    )
    (net (code "3") (name "CAN1_H") (class "Default")
      (node (ref "CF1.2") (pin "33") (pinfunction "33_33") (pintype "passive"))
      (node (ref "CF1.2") (pin "34") (pinfunction "34_34") (pintype "passive"))
      (node (ref "CF2.2") (pin "33") (pinfunction "33_33") (pintype "passive"))
      (node (ref "CF2.2") (pin "34") (pinfunction "34_34") (pintype "passive"))
      (node (ref "CF3.2") (pin "33") (pinfunction "33_33") (pintype "passive"))
      (node (ref "CF3.2") (pin "34") (pinfunction "34_34") (pintype "passive"))
      (node (ref "CF4.2") (pin "33") (pinfunction "33_33") (pintype "passive"))
      (node (ref "CF4.2") (pin "34") (pinfunction "34_34") (pintype "passive"))
      (node (ref "CF5.2") (pin "33") (pinfunction "33_33") (pintype "passive"))
      (node (ref "CF5.2") (pin "34") (pinfunction "34_34") (pintype "passive"))
      (node (ref "CF6.2") (pin "33") (pinfunction "33_33") (pintype "passive"))
      (node (ref "CF6.2") (pin "34") (pinfunction "34_34") (pintype "passive"))
      (node (ref "CF7.2") (pin "33") (pinfunction "33_33") (pintype "passive"))
      (node (ref "CF7.2") (pin "34") (pinfunction "34_34") (pintype "passive"))
      (node (ref "J2") (pin "5") (pinfunction "5_5") (pintype "passive"))
      (node (ref "R1") (pin "1") (pinfunction "1_1") (pintype "passive"))
      (node (ref "R10") (pin "1") (pinfunction "1_1") (pintype "passive"))
      (node (ref "R5") (pin "1") (pinfunction "1_1") (pintype "passive"))
    )
    (net (code "4") (name "CAN1_L") (class "Default")
      (node (ref "CF1.2") (pin "35") (pinfunction "35_35") (pintype "passive"))
      (node (ref "CF1.2") (pin "36") (pinfunction "36_36") (pintype "passive"))
      (node (ref "CF2.2") (pin "35") (pinfunction "35_35") (pintype "passive"))
      (node (ref "CF2.2") (pin "36") (pinfunction "36_36") (pintype "passive"))
      (node (ref "CF3.2") (pin "35") (pinfunction "35_35") (pintype "passive"))
      (node (ref "CF3.2") (pin "36") (pinfunction "36_36") (pintype "passive"))
      (node (ref "CF4.2") (pin "35") (pinfunction "35_35") (pintype "passive"))
      (node (ref "CF4.2") (pin "36") (pinfunction "36_36") (pintype "passive"))
      (node (ref "CF5.2") (pin "35") (pinfunction "35_35") (pintype "passive"))
      (node (ref "CF5.2") (pin "36") (pinfunction "36_36") (pintype "passive"))
      (node (ref "CF6.2") (pin "35") (pinfunction "35_35") (pintype "passive"))
      (node (ref "CF6.2") (pin "36") (pinfunction "36_36") (pintype "passive"))
      (node (ref "CF7.2") (pin "35") (pinfunction "35_35") (pintype "passive"))
      (node (ref "CF7.2") (pin "36") (pinfunction "36_36") (pintype "passive"))
      (node (ref "J2") (pin "4") (pinfunction "4_4") (pintype "passive"))
      (node (ref "R2") (pin "1") (pinfunction "1_1") (pintype "passive"))
      (node (ref "R6") (pin "1") (pinfunction "1_1") (pintype "passive"))
      (node (ref "R9") (pin "1") (pinfunction "1_1") (pintype "passive"))
    )
    (net (code "5") (name "CAN2_H") (class "Default")
      (node (ref "CF1.2") (pin "17") (pinfunction "17_17") (pintype "passive"))
      (node (ref "CF1.2") (pin "18") (pinfunction "18_18") (pintype "passive"))
      (node (ref "CF2.2") (pin "17") (pinfunction "17_17") (pintype "passive"))
      (node (ref "CF2.2") (pin "18") (pinfunction "18_18") (pintype "passive"))
      (node (ref "CF3.2") (pin "17") (pinfunction "17_17") (pintype "passive"))
      (node (ref "CF3.2") (pin "18") (pinfunction "18_18") (pintype "passive"))
      (node (ref "CF4.2") (pin "17") (pinfunction "17_17") (pintype "passive"))
      (node (ref "CF4.2") (pin "18") (pinfunction "18_18") (pintype "passive"))
      (node (ref "CF5.2") (pin "17") (pinfunction "17_17") (pintype "passive"))
      (node (ref "CF5.2") (pin "18") (pinfunction "18_18") (pintype "passive"))
      (node (ref "CF6.2") (pin "17") (pinfunction "17_17") (pintype "passive"))
      (node (ref "CF6.2") (pin "18") (pinfunction "18_18") (pintype "passive"))
      (node (ref "CF7.2") (pin "17") (pinfunction "17_17") (pintype "passive"))
      (node (ref "CF7.2") (pin "18") (pinfunction "18_18") (pintype "passive"))
      (node (ref "J2") (pin "13") (pinfunction "13_13") (pintype "passive"))
      (node (ref "R10") (pin "2") (pinfunction "2_2") (pintype "passive"))
      (node (ref "R3") (pin "1") (pinfunction "1_1") (pintype "passive"))
      (node (ref "R7") (pin "1") (pinfunction "1_1") (pintype "passive"))
    )
    (net (code "6") (name "CAN2_L") (class "Default")
      (node (ref "CF1.2") (pin "19") (pinfunction "19_19") (pintype "passive"))
      (node (ref "CF1.2") (pin "20") (pinfunction "20_20") (pintype "passive"))
      (node (ref "CF2.2") (pin "19") (pinfunction "19_19") (pintype "passive"))
      (node (ref "CF2.2") (pin "20") (pinfunction "20_20") (pintype "passive"))
      (node (ref "CF3.2") (pin "19") (pinfunction "19_19") (pintype "passive"))
      (node (ref "CF3.2") (pin "20") (pinfunction "20_20") (pintype "passive"))
      (node (ref "CF4.2") (pin "19") (pinfunction "19_19") (pintype "passive"))
      (node (ref "CF4.2") (pin "20") (pinfunction "20_20") (pintype "passive"))
      (node (ref "CF5.2") (pin "19") (pinfunction "19_19") (pintype "passive"))
      (node (ref "CF5.2") (pin "20") (pinfunction "20_20") (pintype "passive"))
      (node (ref "CF6.2") (pin "19") (pinfunction "19_19") (pintype "passive"))
      (node (ref "CF6.2") (pin "20") (pinfunction "20_20") (pintype "passive"))
      (node (ref "CF7.2") (pin "19") (pinfunction "19_19") (pintype "passive"))
      (node (ref "CF7.2") (pin "20") (pinfunction "20_20") (pintype "passive"))
      (node (ref "J2") (pin "12") (pinfunction "12_12") (pintype "passive"))
      (node (ref "R4") (pin "1") (pinfunction "1_1") (pintype "passive"))
      (node (ref "R8") (pin "1") (pinfunction "1_1") (pintype "passive"))
      (node (ref "R9") (pin "2") (pinfunction "2_2") (pintype "passive"))
    )
    (net (code "7") (name "GND") (class "Default")
      (node (ref "C1") (pin "2") (pinfunction "2_2") (pintype "passive"))
      (node (ref "C10") (pin "2") (pinfunction "2_2") (pintype "passive"))
      (node (ref "C11") (pin "2") (pinfunction "2_2") (pintype "passive"))
      (node (ref "C2") (pin "2") (pinfunction "2_2") (pintype "passive"))
      (node (ref "C3") (pin "2") (pinfunction "2_2") (pintype "passive"))
      (node (ref "C4") (pin "2") (pinfunction "2_2") (pintype "passive"))
      (node (ref "C5") (pin "2") (pinfunction "2_2") (pintype "passive"))
      (node (ref "C6") (pin "2") (pinfunction "2_2") (pintype "passive"))
      (node (ref "C7") (pin "2") (pinfunction "2_2") (pintype "passive"))
      (node (ref "C8") (pin "2") (pinfunction "2_2") (pintype "passive"))
      (node (ref "C9") (pin "2") (pinfunction "2_2") (pintype "passive"))
      (node (ref "CF1.2") (pin "27") (pinfunction "27_27") (pintype "passive"))
      (node (ref "CF1.2") (pin "28") (pinfunction "28_28") (pintype "passive"))
      (node (ref "CF1.2") (pin "29") (pinfunction "29_29") (pintype "passive"))
      (node (ref "CF1.2") (pin "30") (pinfunction "30_30") (pintype "passive"))
      (node (ref "CF1.2") (pin "LC1") (pinfunction "LC1_LC1") (pintype "passive"))
      (node (ref "CF1.2") (pin "LC2") (pinfunction "LC2_LC2") (pintype "passive"))
      (node (ref "CF2.2") (pin "27") (pinfunction "27_27") (pintype "passive"))
      (node (ref "CF2.2") (pin "28") (pinfunction "28_28") (pintype "passive"))
      (node (ref "CF2.2") (pin "29") (pinfunction "29_29") (pintype "passive"))
      (node (ref "CF2.2") (pin "30") (pinfunction "30_30") (pintype "passive"))
      (node (ref "CF2.2") (pin "LC1") (pinfunction "LC1_LC1") (pintype "passive"))
      (node (ref "CF2.2") (pin "LC2") (pinfunction "LC2_LC2") (pintype "passive"))
      (node (ref "CF3.2") (pin "27") (pinfunction "27_27") (pintype "passive"))
      (node (ref "CF3.2") (pin "28") (pinfunction "28_28") (pintype "passive"))
      (node (ref "CF3.2") (pin "29") (pinfunction "29_29") (pintype "passive"))
      (node (ref "CF3.2") (pin "30") (pinfunction "30_30") (pintype "passive"))
      (node (ref "CF3.2") (pin "LC1") (pinfunction "LC1_LC1") (pintype "passive"))
      (node (ref "CF3.2") (pin "LC2") (pinfunction "LC2_LC2") (pintype "passive"))
      (node (ref "CF4.2") (pin "27") (pinfunction "27_27") (pintype "passive"))
      (node (ref "CF4.2") (pin "28") (pinfunction "28_28") (pintype "passive"))
      (node (ref "CF4.2") (pin "29") (pinfunction "29_29") (pintype "passive"))
      (node (ref "CF4.2") (pin "30") (pinfunction "30_30") (pintype "passive"))
      (node (ref "CF4.2") (pin "LC1") (pinfunction "LC1_LC1") (pintype "passive"))
      (node (ref "CF4.2") (pin "LC2") (pinfunction "LC2_LC2") (pintype "passive"))
      (node (ref "CF5.2") (pin "27") (pinfunction "27_27") (pintype "passive"))
      (node (ref "CF5.2") (pin "28") (pinfunction "28_28") (pintype "passive"))
      (node (ref "CF5.2") (pin "29") (pinfunction "29_29") (pintype "passive"))
      (node (ref "CF5.2") (pin "30") (pinfunction "30_30") (pintype "passive"))
      (node (ref "CF5.2") (pin "LC1") (pinfunction "LC1_LC1") (pintype "passive"))
      (node (ref "CF5.2") (pin "LC2") (pinfunction "LC2_LC2") (pintype "passive"))
      (node (ref "CF6.2") (pin "27") (pinfunction "27_27") (pintype "passive"))
      (node (ref "CF6.2") (pin "28") (pinfunction "28_28") (pintype "passive"))
      (node (ref "CF6.2") (pin "29") (pinfunction "29_29") (pintype "passive"))
      (node (ref "CF6.2") (pin "30") (pinfunction "30_30") (pintype "passive"))
      (node (ref "CF6.2") (pin "LC1") (pinfunction "LC1_LC1") (pintype "passive"))
      (node (ref "CF6.2") (pin "LC2") (pinfunction "LC2_LC2") (pintype "passive"))
      (node (ref "CF7.2") (pin "27") (pinfunction "27_27") (pintype "passive"))
      (node (ref "CF7.2") (pin "28") (pinfunction "28_28") (pintype "passive"))
      (node (ref "CF7.2") (pin "29") (pinfunction "29_29") (pintype "passive"))
      (node (ref "CF7.2") (pin "30") (pinfunction "30_30") (pintype "passive"))
      (node (ref "CF7.2") (pin "LC1") (pinfunction "LC1_LC1") (pintype "passive"))
      (node (ref "CF7.2") (pin "LC2") (pinfunction "LC2_LC2") (pintype "passive"))
      (node (ref "CM1.1") (pin "P$1") (pinfunction "SHIELD1_P$1") (pintype "passive"))
      (node (ref "CM1.1") (pin "P$2") (pinfunction "SHIELD1_P$2") (pintype "passive"))
      (node (ref "CM1.1") (pin "P$3") (pinfunction "SHIELD1_P$3") (pintype "passive"))
      (node (ref "CM1.1") (pin "P$4") (pinfunction "SHIELD1_P$4") (pintype "passive"))
      (node (ref "CM1.2") (pin "P$1") (pinfunction "SHIELD1_P$1") (pintype "passive"))
      (node (ref "CM1.2") (pin "P$2") (pinfunction "SHIELD1_P$2") (pintype "passive"))
      (node (ref "CM1.2") (pin "P$3") (pinfunction "SHIELD1_P$3") (pintype "passive"))
      (node (ref "CM1.2") (pin "P$4") (pinfunction "SHIELD1_P$4") (pintype "passive"))
      (node (ref "CM1.3") (pin "P$1") (pinfunction "SHIELD1_P$1") (pintype "passive"))
      (node (ref "CM1.3") (pin "P$2") (pinfunction "SHIELD1_P$2") (pintype "passive"))
      (node (ref "CM1.3") (pin "P$3") (pinfunction "SHIELD1_P$3") (pintype "passive"))
      (node (ref "CM1.3") (pin "P$4") (pinfunction "SHIELD1_P$4") (pintype "passive"))
      (node (ref "CM2.2") (pin "P$1") (pinfunction "SHIELD1_P$1") (pintype "passive"))
      (node (ref "CM2.2") (pin "P$2") (pinfunction "SHIELD1_P$2") (pintype "passive"))
      (node (ref "CM2.2") (pin "P$3") (pinfunction "SHIELD1_P$3") (pintype "passive"))
      (node (ref "CM2.2") (pin "P$4") (pinfunction "SHIELD1_P$4") (pintype "passive"))
      (node (ref "CM2.3") (pin "P$1") (pinfunction "SHIELD1_P$1") (pintype "passive"))
      (node (ref "CM2.3") (pin "P$2") (pinfunction "SHIELD1_P$2") (pintype "passive"))
      (node (ref "CM2.3") (pin "P$3") (pinfunction "SHIELD1_P$3") (pintype "passive"))
      (node (ref "CM2.3") (pin "P$4") (pinfunction "SHIELD1_P$4") (pintype "passive"))
      (node (ref "CM3.2") (pin "P$1") (pinfunction "SHIELD1_P$1") (pintype "passive"))
      (node (ref "CM3.2") (pin "P$2") (pinfunction "SHIELD1_P$2") (pintype "passive"))
      (node (ref "CM3.2") (pin "P$3") (pinfunction "SHIELD1_P$3") (pintype "passive"))
      (node (ref "CM3.2") (pin "P$4") (pinfunction "SHIELD1_P$4") (pintype "passive"))
      (node (ref "CM4.1") (pin "P$1") (pinfunction "SHIELD1_P$1") (pintype "passive"))
      (node (ref "CM4.1") (pin "P$2") (pinfunction "SHIELD1_P$2") (pintype "passive"))
      (node (ref "CM4.1") (pin "P$3") (pinfunction "SHIELD1_P$3") (pintype "passive"))
      (node (ref "CM4.1") (pin "P$4") (pinfunction "SHIELD1_P$4") (pintype "passive"))
      (node (ref "CM8") (pin "2") (pinfunction "P$2_2") (pintype "bidirectional"))
      (node (ref "CM8") (pin "3") (pinfunction "P$2_3") (pintype "bidirectional"))
      (node (ref "J1") (pin "HD1") (pinfunction "HD_HD1") (pintype "passive"))
      (node (ref "J1") (pin "HD2") (pinfunction "HD_HD2") (pintype "passive"))
      (node (ref "J1") (pin "HD3") (pinfunction "HD_HD3") (pintype "passive"))
      (node (ref "J2") (pin "10") (pinfunction "10_10") (pintype "passive"))
      (node (ref "J2") (pin "19") (pinfunction "17_19") (pintype "passive"))
      (node (ref "J2") (pin "20") (pinfunction "17_20") (pintype "passive"))
      (node (ref "J2") (pin "21") (pinfunction "17_21") (pintype "passive"))
      (node (ref "J2") (pin "22") (pinfunction "17_22") (pintype "passive"))
      (node (ref "J2") (pin "6") (pinfunction "6_6") (pintype "passive"))
      (node (ref "J2") (pin "8") (pinfunction "8_8") (pintype "passive"))
    )
    (net (code "8") (name "L-TURNSTILE") (class "Default")
      (node (ref "CM1.2") (pin "RF-DOWN") (pinfunction "RF_RF-DOWN") (pintype "passive"))
      (node (ref "CM2.2") (pin "RF-DOWN") (pinfunction "RF_RF-DOWN") (pintype "passive"))
    )
    (net (code "9") (name "L1-TURNSTILE") (class "Default")
      (node (ref "CM1.1") (pin "RF-DOWN") (pinfunction "RF_RF-DOWN") (pintype "passive"))
      (node (ref "CM3.2") (pin "RF-DOWN") (pinfunction "RF_RF-DOWN") (pintype "passive"))
    )
    (net (code "10") (name "Net-(C1-Pad1)") (class "Default")
      (node (ref "C1") (pin "1") (pinfunction "1_1") (pintype "passive"))
      (node (ref "R1") (pin "2") (pinfunction "2_2") (pintype "passive"))
      (node (ref "R2") (pin "2") (pinfunction "2_2") (pintype "passive"))
    )
    (net (code "11") (name "Net-(C2-Pad1)") (class "Default")
      (node (ref "C2") (pin "1") (pinfunction "1_1") (pintype "passive"))
      (node (ref "R3") (pin "2") (pinfunction "2_2") (pintype "passive"))
      (node (ref "R4") (pin "2") (pinfunction "2_2") (pintype "passive"))
    )
    (net (code "12") (name "Net-(C3-Pad1)") (class "Default")
      (node (ref "C3") (pin "1") (pinfunction "1_1") (pintype "passive"))
      (node (ref "R5") (pin "2") (pinfunction "2_2") (pintype "passive"))
      (node (ref "R6") (pin "2") (pinfunction "2_2") (pintype "passive"))
    )
    (net (code "13") (name "Net-(C4-Pad1)") (class "Default")
      (node (ref "C4") (pin "1") (pinfunction "1_1") (pintype "passive"))
      (node (ref "R7") (pin "2") (pinfunction "2_2") (pintype "passive"))
      (node (ref "R8") (pin "2") (pinfunction "2_2") (pintype "passive"))
    )
    (net (code "14") (name "OPD_PWR") (class "Default")
      (node (ref "CF1.2") (pin "15") (pinfunction "15_15") (pintype "passive"))
      (node (ref "CF1.2") (pin "16") (pinfunction "16_16") (pintype "passive"))
      (node (ref "CF2.2") (pin "15") (pinfunction "15_15") (pintype "passive"))
      (node (ref "CF2.2") (pin "16") (pinfunction "16_16") (pintype "passive"))
      (node (ref "CF3.2") (pin "15") (pinfunction "15_15") (pintype "passive"))
      (node (ref "CF3.2") (pin "16") (pinfunction "16_16") (pintype "passive"))
      (node (ref "CF4.2") (pin "15") (pinfunction "15_15") (pintype "passive"))
      (node (ref "CF4.2") (pin "16") (pinfunction "16_16") (pintype "passive"))
      (node (ref "CF5.2") (pin "15") (pinfunction "15_15") (pintype "passive"))
      (node (ref "CF5.2") (pin "16") (pinfunction "16_16") (pintype "passive"))
      (node (ref "CF6.2") (pin "15") (pinfunction "15_15") (pintype "passive"))
      (node (ref "CF6.2") (pin "16") (pinfunction "16_16") (pintype "passive"))
      (node (ref "CF7.2") (pin "15") (pinfunction "15_15") (pintype "passive"))
      (node (ref "CF7.2") (pin "16") (pinfunction "16_16") (pintype "passive"))
      (node (ref "J2") (pin "14") (pinfunction "14_14") (pintype "passive"))
    )
    (net (code "15") (name "OPD_SCL") (class "Default")
      (node (ref "CF1.2") (pin "13") (pinfunction "13_13") (pintype "passive"))
      (node (ref "CF1.2") (pin "14") (pinfunction "14_14") (pintype "passive"))
      (node (ref "CF2.2") (pin "13") (pinfunction "13_13") (pintype "passive"))
      (node (ref "CF2.2") (pin "14") (pinfunction "14_14") (pintype "passive"))
      (node (ref "CF3.2") (pin "13") (pinfunction "13_13") (pintype "passive"))
      (node (ref "CF3.2") (pin "14") (pinfunction "14_14") (pintype "passive"))
      (node (ref "CF4.2") (pin "13") (pinfunction "13_13") (pintype "passive"))
      (node (ref "CF4.2") (pin "14") (pinfunction "14_14") (pintype "passive"))
      (node (ref "CF5.2") (pin "13") (pinfunction "13_13") (pintype "passive"))
      (node (ref "CF5.2") (pin "14") (pinfunction "14_14") (pintype "passive"))
      (node (ref "CF6.2") (pin "13") (pinfunction "13_13") (pintype "passive"))
      (node (ref "CF6.2") (pin "14") (pinfunction "14_14") (pintype "passive"))
      (node (ref "CF7.2") (pin "13") (pinfunction "13_13") (pintype "passive"))
      (node (ref "CF7.2") (pin "14") (pinfunction "14_14") (pintype "passive"))
      (node (ref "J2") (pin "15") (pinfunction "15_15") (pintype "passive"))
    )
    (net (code "16") (name "OPD_SDA") (class "Default")
      (node (ref "CF1.2") (pin "11") (pinfunction "11_11") (pintype "passive"))
      (node (ref "CF1.2") (pin "12") (pinfunction "12_12") (pintype "passive"))
      (node (ref "CF2.2") (pin "11") (pinfunction "11_11") (pintype "passive"))
      (node (ref "CF2.2") (pin "12") (pinfunction "12_12") (pintype "passive"))
      (node (ref "CF3.2") (pin "11") (pinfunction "11_11") (pintype "passive"))
      (node (ref "CF3.2") (pin "12") (pinfunction "12_12") (pintype "passive"))
      (node (ref "CF4.2") (pin "11") (pinfunction "11_11") (pintype "passive"))
      (node (ref "CF4.2") (pin "12") (pinfunction "12_12") (pintype "passive"))
      (node (ref "CF5.2") (pin "11") (pinfunction "11_11") (pintype "passive"))
      (node (ref "CF5.2") (pin "12") (pinfunction "12_12") (pintype "passive"))
      (node (ref "CF6.2") (pin "11") (pinfunction "11_11") (pintype "passive"))
      (node (ref "CF6.2") (pin "12") (pinfunction "12_12") (pintype "passive"))
      (node (ref "CF7.2") (pin "11") (pinfunction "11_11") (pintype "passive"))
      (node (ref "CF7.2") (pin "12") (pinfunction "12_12") (pintype "passive"))
      (node (ref "J2") (pin "16") (pinfunction "16_16") (pintype "passive"))
    )
    (net (code "17") (name "S-PATCH") (class "Default")
      (node (ref "CM4.1") (pin "RF-DOWN") (pinfunction "RF_RF-DOWN") (pintype "passive"))
      (node (ref "CM8") (pin "1") (pinfunction "P$1_1") (pintype "bidirectional"))
    )
    (net (code "18") (name "SPARE1") (class "Default")
      (node (ref "CF1.2") (pin "1") (pinfunction "1_1") (pintype "passive"))
      (node (ref "CF1.2") (pin "2") (pinfunction "2_2") (pintype "passive"))
      (node (ref "CF2.2") (pin "1") (pinfunction "1_1") (pintype "passive"))
      (node (ref "CF2.2") (pin "2") (pinfunction "2_2") (pintype "passive"))
      (node (ref "CF3.2") (pin "1") (pinfunction "1_1") (pintype "passive"))
      (node (ref "CF3.2") (pin "2") (pinfunction "2_2") (pintype "passive"))
      (node (ref "CF4.2") (pin "1") (pinfunction "1_1") (pintype "passive"))
      (node (ref "CF4.2") (pin "2") (pinfunction "2_2") (pintype "passive"))
      (node (ref "CF5.2") (pin "1") (pinfunction "1_1") (pintype "passive"))
      (node (ref "CF5.2") (pin "2") (pinfunction "2_2") (pintype "passive"))
      (node (ref "CF6.2") (pin "1") (pinfunction "1_1") (pintype "passive"))
      (node (ref "CF6.2") (pin "2") (pinfunction "2_2") (pintype "passive"))
      (node (ref "CF7.2") (pin "1") (pinfunction "1_1") (pintype "passive"))
      (node (ref "CF7.2") (pin "2") (pinfunction "2_2") (pintype "passive"))
      (node (ref "J1") (pin "19") (pinfunction "19_19") (pintype "passive"))
      (node (ref "J1") (pin "20") (pinfunction "20_20") (pintype "passive"))
    )
    (net (code "19") (name "SPARE3") (class "Default")
      (node (ref "CF1.2") (pin "3") (pinfunction "3_3") (pintype "passive"))
      (node (ref "CF2.2") (pin "3") (pinfunction "3_3") (pintype "passive"))
      (node (ref "CF3.2") (pin "3") (pinfunction "3_3") (pintype "passive"))
      (node (ref "CF4.2") (pin "3") (pinfunction "3_3") (pintype "passive"))
      (node (ref "CF5.2") (pin "3") (pinfunction "3_3") (pintype "passive"))
      (node (ref "CF6.2") (pin "3") (pinfunction "3_3") (pintype "passive"))
      (node (ref "CF7.2") (pin "3") (pinfunction "3_3") (pintype "passive"))
      (node (ref "J1") (pin "18") (pinfunction "18_18") (pintype "passive"))
    )
    (net (code "20") (name "SPARE4") (class "Default")
      (node (ref "CF1.2") (pin "4") (pinfunction "4_4") (pintype "passive"))
      (node (ref "CF2.2") (pin "4") (pinfunction "4_4") (pintype "passive"))
      (node (ref "CF3.2") (pin "4") (pinfunction "4_4") (pintype "passive"))
      (node (ref "CF4.2") (pin "4") (pinfunction "4_4") (pintype "passive"))
      (node (ref "CF5.2") (pin "4") (pinfunction "4_4") (pintype "passive"))
      (node (ref "CF6.2") (pin "4") (pinfunction "4_4") (pintype "passive"))
      (node (ref "CF7.2") (pin "4") (pinfunction "4_4") (pintype "passive"))
      (node (ref "J1") (pin "17") (pinfunction "17_17") (pintype "passive"))
    )
    (net (code "21") (name "SPARE5") (class "Default")
      (node (ref "CF1.2") (pin "5") (pinfunction "5_5") (pintype "passive"))
      (node (ref "CF2.2") (pin "5") (pinfunction "5_5") (pintype "passive"))
      (node (ref "CF3.2") (pin "5") (pinfunction "5_5") (pintype "passive"))
      (node (ref "CF4.2") (pin "5") (pinfunction "5_5") (pintype "passive"))
      (node (ref "CF5.2") (pin "5") (pinfunction "5_5") (pintype "passive"))
      (node (ref "CF6.2") (pin "5") (pinfunction "5_5") (pintype "passive"))
      (node (ref "CF7.2") (pin "5") (pinfunction "5_5") (pintype "passive"))
      (node (ref "J1") (pin "16") (pinfunction "16_16") (pintype "passive"))
    )
    (net (code "22") (name "SPARE6") (class "Default")
      (node (ref "CF1.2") (pin "6") (pinfunction "6_6") (pintype "passive"))
      (node (ref "CF2.2") (pin "6") (pinfunction "6_6") (pintype "passive"))
      (node (ref "CF3.2") (pin "6") (pinfunction "6_6") (pintype "passive"))
      (node (ref "CF4.2") (pin "6") (pinfunction "6_6") (pintype "passive"))
      (node (ref "CF5.2") (pin "6") (pinfunction "6_6") (pintype "passive"))
      (node (ref "CF6.2") (pin "6") (pinfunction "6_6") (pintype "passive"))
      (node (ref "CF7.2") (pin "6") (pinfunction "6_6") (pintype "passive"))
      (node (ref "J1") (pin "15") (pinfunction "15_15") (pintype "passive"))
    )
    (net (code "23") (name "SPARE7") (class "Default")
      (node (ref "CF1.2") (pin "7") (pinfunction "7_7") (pintype "passive"))
      (node (ref "CF2.2") (pin "7") (pinfunction "7_7") (pintype "passive"))
      (node (ref "CF3.2") (pin "7") (pinfunction "7_7") (pintype "passive"))
      (node (ref "CF4.2") (pin "7") (pinfunction "7_7") (pintype "passive"))
      (node (ref "CF5.2") (pin "7") (pinfunction "7_7") (pintype "passive"))
      (node (ref "CF6.2") (pin "7") (pinfunction "7_7") (pintype "passive"))
      (node (ref "CF7.2") (pin "7") (pinfunction "7_7") (pintype "passive"))
      (node (ref "J1") (pin "14") (pinfunction "14_14") (pintype "passive"))
    )
    (net (code "24") (name "SPARE8") (class "Default")
      (node (ref "CF1.2") (pin "8") (pinfunction "8_8") (pintype "passive"))
      (node (ref "CF2.2") (pin "8") (pinfunction "8_8") (pintype "passive"))
      (node (ref "CF3.2") (pin "8") (pinfunction "8_8") (pintype "passive"))
      (node (ref "CF4.2") (pin "8") (pinfunction "8_8") (pintype "passive"))
      (node (ref "CF5.2") (pin "8") (pinfunction "8_8") (pintype "passive"))
      (node (ref "CF6.2") (pin "8") (pinfunction "8_8") (pintype "passive"))
      (node (ref "CF7.2") (pin "8") (pinfunction "8_8") (pintype "passive"))
      (node (ref "J1") (pin "13") (pinfunction "13_13") (pintype "passive"))
    )
    (net (code "25") (name "SPARE9") (class "Default")
      (node (ref "CF1.2") (pin "9") (pinfunction "9_9") (pintype "passive"))
      (node (ref "CF2.2") (pin "9") (pinfunction "9_9") (pintype "passive"))
      (node (ref "CF3.2") (pin "9") (pinfunction "9_9") (pintype "passive"))
      (node (ref "CF4.2") (pin "9") (pinfunction "9_9") (pintype "passive"))
      (node (ref "CF5.2") (pin "9") (pinfunction "9_9") (pintype "passive"))
      (node (ref "CF6.2") (pin "9") (pinfunction "9_9") (pintype "passive"))
      (node (ref "CF7.2") (pin "9") (pinfunction "9_9") (pintype "passive"))
      (node (ref "J1") (pin "12") (pinfunction "12_12") (pintype "passive"))
    )
    (net (code "26") (name "SPARE10") (class "Default")
      (node (ref "CF1.2") (pin "10") (pinfunction "10_10") (pintype "passive"))
      (node (ref "CF2.2") (pin "10") (pinfunction "10_10") (pintype "passive"))
      (node (ref "CF3.2") (pin "10") (pinfunction "10_10") (pintype "passive"))
      (node (ref "CF4.2") (pin "10") (pinfunction "10_10") (pintype "passive"))
      (node (ref "CF5.2") (pin "10") (pinfunction "10_10") (pintype "passive"))
      (node (ref "CF6.2") (pin "10") (pinfunction "10_10") (pintype "passive"))
      (node (ref "CF7.2") (pin "10") (pinfunction "10_10") (pintype "passive"))
      (node (ref "J1") (pin "11") (pinfunction "11_11") (pintype "passive"))
    )
    (net (code "27") (name "SPARE21") (class "Default")
      (node (ref "CF1.2") (pin "21") (pinfunction "21_21") (pintype "passive"))
      (node (ref "CF2.2") (pin "21") (pinfunction "21_21") (pintype "passive"))
      (node (ref "CF3.2") (pin "21") (pinfunction "21_21") (pintype "passive"))
      (node (ref "CF4.2") (pin "21") (pinfunction "21_21") (pintype "passive"))
      (node (ref "CF5.2") (pin "21") (pinfunction "21_21") (pintype "passive"))
      (node (ref "CF6.2") (pin "21") (pinfunction "21_21") (pintype "passive"))
      (node (ref "CF7.2") (pin "21") (pinfunction "21_21") (pintype "passive"))
    )
    (net (code "28") (name "SPARE22") (class "Default")
      (node (ref "CF1.2") (pin "22") (pinfunction "22_22") (pintype "passive"))
      (node (ref "CF2.2") (pin "22") (pinfunction "22_22") (pintype "passive"))
      (node (ref "CF3.2") (pin "22") (pinfunction "22_22") (pintype "passive"))
      (node (ref "CF4.2") (pin "22") (pinfunction "22_22") (pintype "passive"))
      (node (ref "CF5.2") (pin "22") (pinfunction "22_22") (pintype "passive"))
      (node (ref "CF6.2") (pin "22") (pinfunction "22_22") (pintype "passive"))
      (node (ref "CF7.2") (pin "22") (pinfunction "22_22") (pintype "passive"))
    )
    (net (code "29") (name "SPARE31") (class "Default")
      (node (ref "CF1.2") (pin "31") (pinfunction "31_31") (pintype "passive"))
      (node (ref "CF2.2") (pin "31") (pinfunction "31_31") (pintype "passive"))
      (node (ref "CF3.2") (pin "31") (pinfunction "31_31") (pintype "passive"))
      (node (ref "CF4.2") (pin "31") (pinfunction "31_31") (pintype "passive"))
      (node (ref "CF5.2") (pin "31") (pinfunction "31_31") (pintype "passive"))
      (node (ref "CF6.2") (pin "31") (pinfunction "31_31") (pintype "passive"))
      (node (ref "CF7.2") (pin "31") (pinfunction "31_31") (pintype "passive"))
    )
    (net (code "30") (name "SPARE32") (class "Default")
      (node (ref "CF1.2") (pin "32") (pinfunction "32_32") (pintype "passive"))
      (node (ref "CF2.2") (pin "32") (pinfunction "32_32") (pintype "passive"))
      (node (ref "CF3.2") (pin "32") (pinfunction "32_32") (pintype "passive"))
      (node (ref "CF4.2") (pin "32") (pinfunction "32_32") (pintype "passive"))
      (node (ref "CF5.2") (pin "32") (pinfunction "32_32") (pintype "passive"))
      (node (ref "CF6.2") (pin "32") (pinfunction "32_32") (pintype "passive"))
      (node (ref "CF7.2") (pin "32") (pinfunction "32_32") (pintype "passive"))
    )
    (net (code "31") (name "UHF-TURNSTILE") (class "Default")
      (node (ref "CM1.3") (pin "RF-DOWN") (pinfunction "RF_RF-DOWN") (pintype "passive"))
      (node (ref "CM2.3") (pin "RF-DOWN") (pinfunction "RF_RF-DOWN") (pintype "passive"))
    )
    (net (code "32") (name "VBUS") (class "Default")
      (node (ref "C10") (pin "1") (pinfunction "1_1") (pintype "passive"))
      (node (ref "C11") (pin "1") (pinfunction "1_1") (pintype "passive"))
      (node (ref "C5") (pin "1") (pinfunction "1_1") (pintype "passive"))
      (node (ref "C6") (pin "1") (pinfunction "1_1") (pintype "passive"))
      (node (ref "C7") (pin "1") (pinfunction "1_1") (pintype "passive"))
      (node (ref "C8") (pin "1") (pinfunction "1_1") (pintype "passive"))
      (node (ref "C9") (pin "1") (pinfunction "1_1") (pintype "passive"))
      (node (ref "CF1.2") (pin "23") (pinfunction "23_23") (pintype "passive"))
      (node (ref "CF1.2") (pin "24") (pinfunction "24_24") (pintype "passive"))
      (node (ref "CF1.2") (pin "25") (pinfunction "25_25") (pintype "passive"))
      (node (ref "CF1.2") (pin "26") (pinfunction "26_26") (pintype "passive"))
      (node (ref "CF2.2") (pin "23") (pinfunction "23_23") (pintype "passive"))
      (node (ref "CF2.2") (pin "24") (pinfunction "24_24") (pintype "passive"))
      (node (ref "CF2.2") (pin "25") (pinfunction "25_25") (pintype "passive"))
      (node (ref "CF2.2") (pin "26") (pinfunction "26_26") (pintype "passive"))
      (node (ref "CF3.2") (pin "23") (pinfunction "23_23") (pintype "passive"))
      (node (ref "CF3.2") (pin "24") (pinfunction "24_24") (pintype "passive"))
      (node (ref "CF3.2") (pin "25") (pinfunction "25_25") (pintype "passive"))
      (node (ref "CF3.2") (pin "26") (pinfunction "26_26") (pintype "passive"))
      (node (ref "CF4.2") (pin "23") (pinfunction "23_23") (pintype "passive"))
      (node (ref "CF4.2") (pin "24") (pinfunction "24_24") (pintype "passive"))
      (node (ref "CF4.2") (pin "25") (pinfunction "25_25") (pintype "passive"))
      (node (ref "CF4.2") (pin "26") (pinfunction "26_26") (pintype "passive"))
      (node (ref "CF5.2") (pin "23") (pinfunction "23_23") (pintype "passive"))
      (node (ref "CF5.2") (pin "24") (pinfunction "24_24") (pintype "passive"))
      (node (ref "CF5.2") (pin "25") (pinfunction "25_25") (pintype "passive"))
      (node (ref "CF5.2") (pin "26") (pinfunction "26_26") (pintype "passive"))
      (node (ref "CF6.2") (pin "23") (pinfunction "23_23") (pintype "passive"))
      (node (ref "CF6.2") (pin "24") (pinfunction "24_24") (pintype "passive"))
      (node (ref "CF6.2") (pin "25") (pinfunction "25_25") (pintype "passive"))
      (node (ref "CF6.2") (pin "26") (pinfunction "26_26") (pintype "passive"))
      (node (ref "CF7.2") (pin "23") (pinfunction "23_23") (pintype "passive"))
      (node (ref "CF7.2") (pin "24") (pinfunction "24_24") (pintype "passive"))
      (node (ref "CF7.2") (pin "25") (pinfunction "25_25") (pintype "passive"))
      (node (ref "CF7.2") (pin "26") (pinfunction "26_26") (pintype "passive"))
      (node (ref "J2") (pin "11") (pinfunction "11_11") (pintype "passive"))
      (node (ref "J2") (pin "7") (pinfunction "7_7") (pintype "passive"))
      (node (ref "J2") (pin "9") (pinfunction "9_9") (pintype "passive"))
    )
    (net (code "33") (name "unconnected-(FIDUCIAL1-PadFIDUCIAL)") (class "Default")
      (node (ref "FIDUCIAL1") (pin "FIDUCIAL") (pinfunction "FIDUCIAL_FIDUCIAL") (pintype "no_connect"))
    )
    (net (code "34") (name "unconnected-(FIDUCIAL2-PadFIDUCIAL)") (class "Default")
      (node (ref "FIDUCIAL2") (pin "FIDUCIAL") (pinfunction "FIDUCIAL_FIDUCIAL") (pintype "no_connect"))
    )
    (net (code "35") (name "unconnected-(FIDUCIAL3-PadFIDUCIAL)") (class "Default")
      (node (ref "FIDUCIAL3") (pin "FIDUCIAL") (pinfunction "FIDUCIAL_FIDUCIAL") (pintype "no_connect"))
    )
    (net (code "36") (name "unconnected-(J1-Pad1)") (class "Default")
      (node (ref "J1") (pin "1") (pinfunction "1_1") (pintype "passive"))
    )
    (net (code "37") (name "unconnected-(J1-Pad2)") (class "Default")
      (node (ref "J1") (pin "2") (pinfunction "2_2") (pintype "passive"))
    )
    (net (code "38") (name "unconnected-(J1-Pad3)") (class "Default")
      (node (ref "J1") (pin "3") (pinfunction "3_3") (pintype "passive"))
    )
    (net (code "39") (name "unconnected-(J1-Pad4)") (class "Default")
      (node (ref "J1") (pin "4") (pinfunction "4_4") (pintype "passive"))
    )
    (net (code "40") (name "unconnected-(J1-Pad5)") (class "Default")
      (node (ref "J1") (pin "5") (pinfunction "5_5") (pintype "passive"))
    )
    (net (code "41") (name "unconnected-(J1-Pad6)") (class "Default")
      (node (ref "J1") (pin "6") (pinfunction "6_6") (pintype "passive"))
    )
    (net (code "42") (name "unconnected-(J1-Pad7)") (class "Default")
      (node (ref "J1") (pin "7") (pinfunction "7_7") (pintype "passive"))
    )
    (net (code "43") (name "unconnected-(J1-Pad8)") (class "Default")
      (node (ref "J1") (pin "8") (pinfunction "8_8") (pintype "passive"))
    )
    (net (code "44") (name "unconnected-(J1-Pad9)") (class "Default")
      (node (ref "J1") (pin "9") (pinfunction "9_9") (pintype "passive"))
    )
    (net (code "45") (name "unconnected-(J1-Pad10)") (class "Default")
      (node (ref "J1") (pin "10") (pinfunction "10_10") (pintype "passive"))
    )
    (net (code "46") (name "~{SD}") (class "Default")
      (node (ref "CF1.2") (pin "39") (pinfunction "39_39") (pintype "passive"))
      (node (ref "CF1.2") (pin "40") (pinfunction "40_40") (pintype "passive"))
      (node (ref "CF2.2") (pin "39") (pinfunction "39_39") (pintype "passive"))
      (node (ref "CF2.2") (pin "40") (pinfunction "40_40") (pintype "passive"))
      (node (ref "CF3.2") (pin "39") (pinfunction "39_39") (pintype "passive"))
      (node (ref "CF3.2") (pin "40") (pinfunction "40_40") (pintype "passive"))
      (node (ref "CF4.2") (pin "39") (pinfunction "39_39") (pintype "passive"))
      (node (ref "CF4.2") (pin "40") (pinfunction "40_40") (pintype "passive"))
      (node (ref "CF5.2") (pin "39") (pinfunction "39_39") (pintype "passive"))
      (node (ref "CF5.2") (pin "40") (pinfunction "40_40") (pintype "passive"))
      (node (ref "CF6.2") (pin "39") (pinfunction "39_39") (pintype "passive"))
      (node (ref "CF6.2") (pin "40") (pinfunction "40_40") (pintype "passive"))
      (node (ref "CF7.2") (pin "39") (pinfunction "39_39") (pintype "passive"))
      (node (ref "CF7.2") (pin "40") (pinfunction "40_40") (pintype "passive"))
      (node (ref "J2") (pin "1") (pinfunction "1_1") (pintype "passive"))
    )
  )
)
